# ImageProc.net
KiCad netlist of a schematic drawn in EAGLE
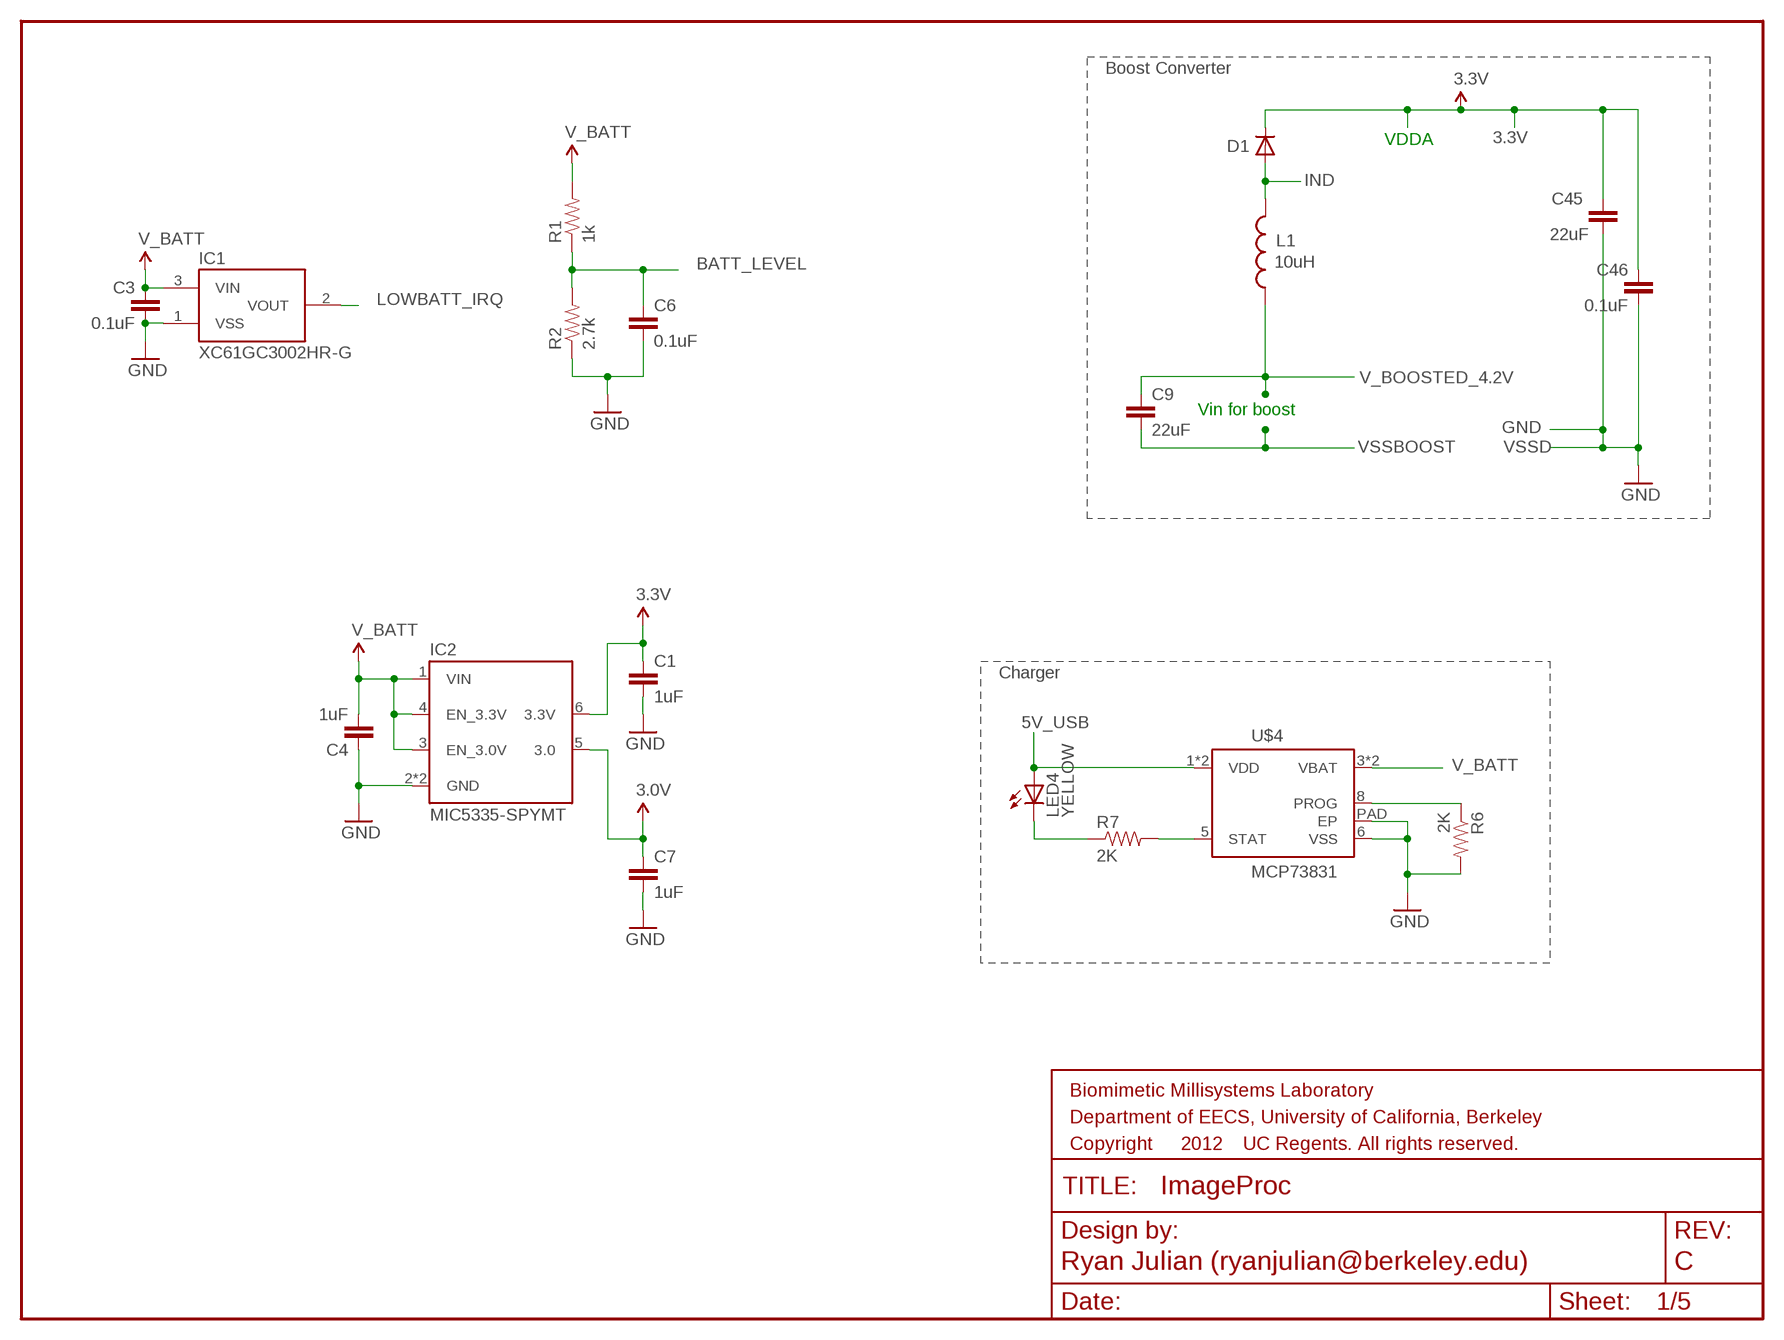
[diagram p0: schematic, sheet 1]
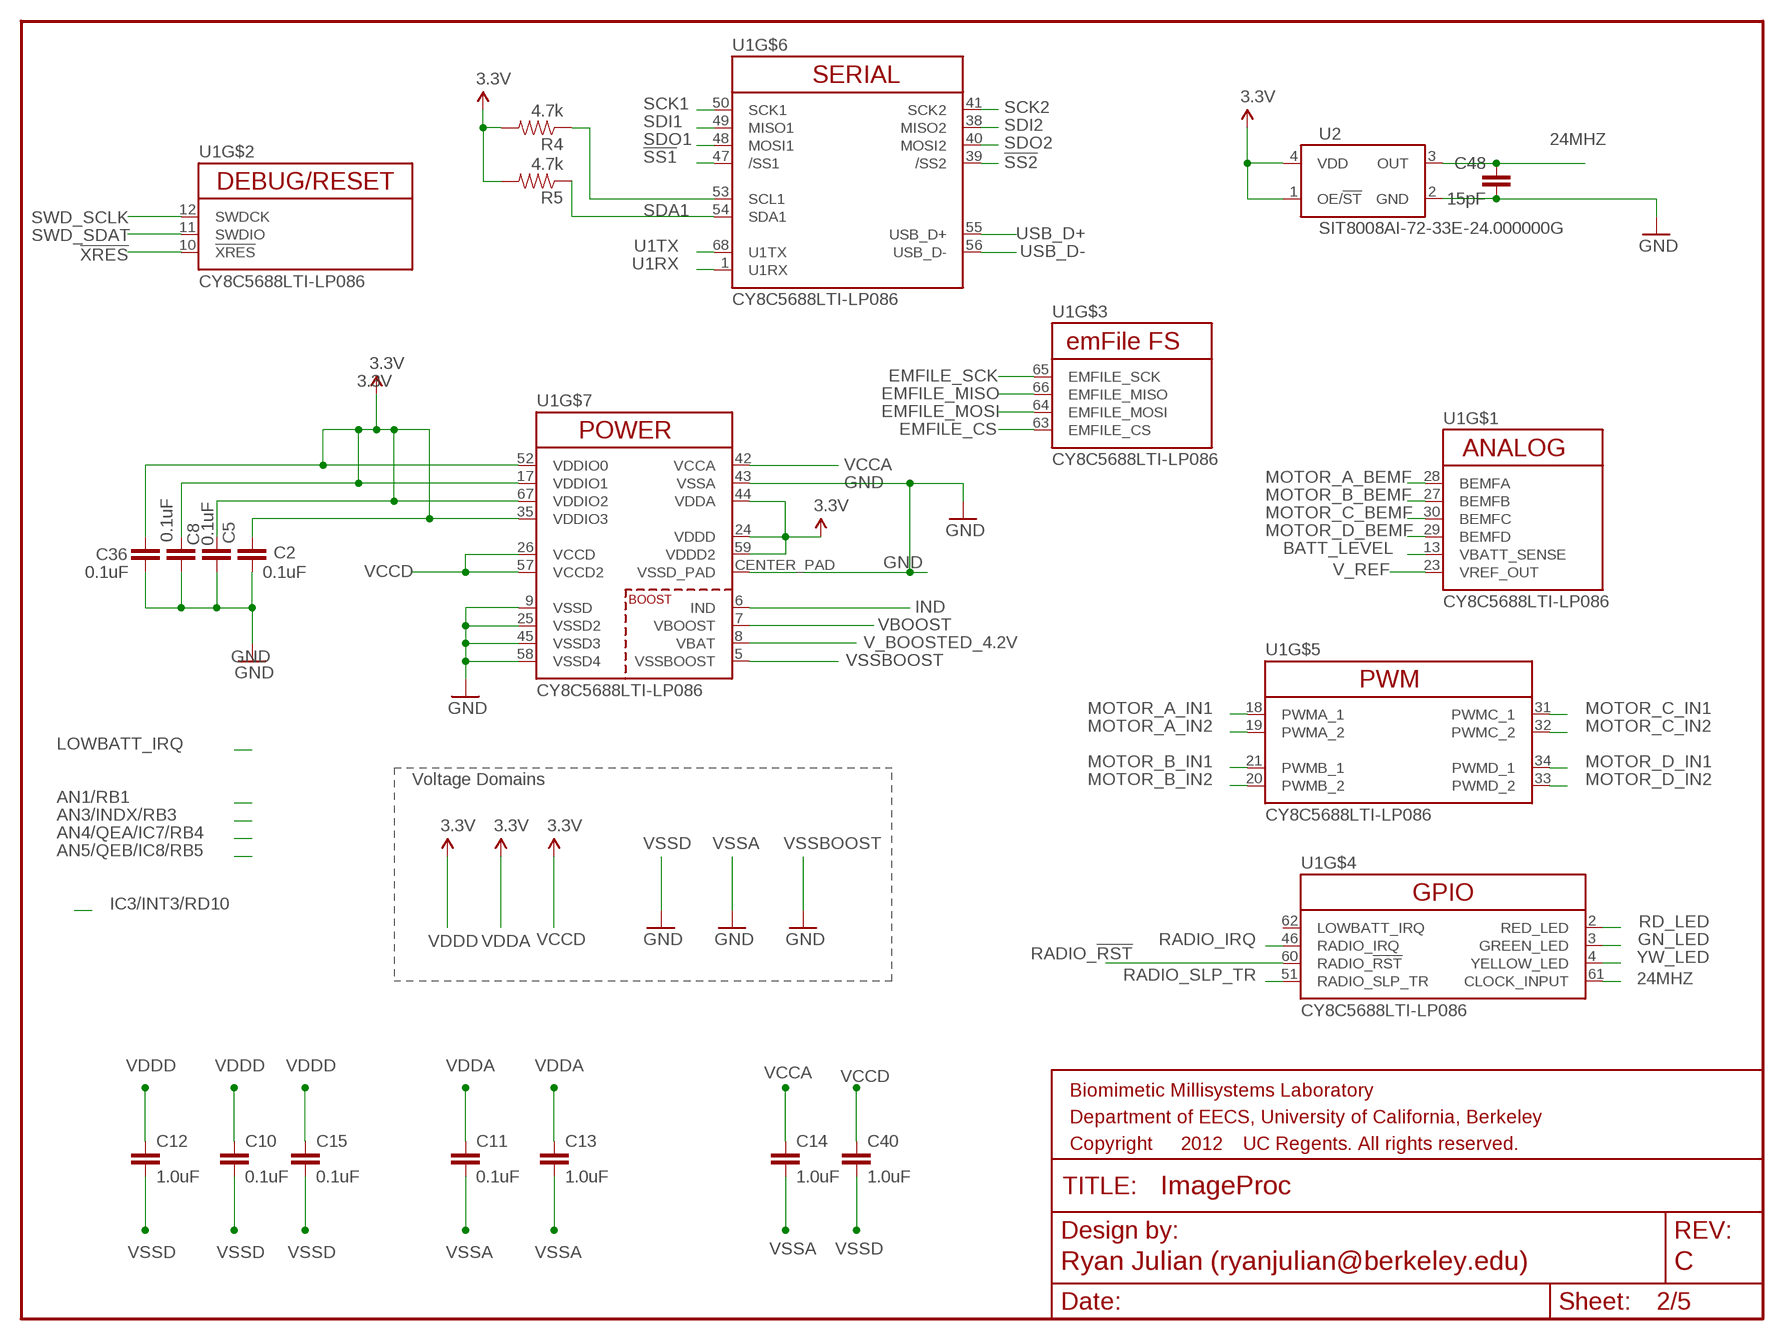
[diagram p1: schematic, sheet 2]
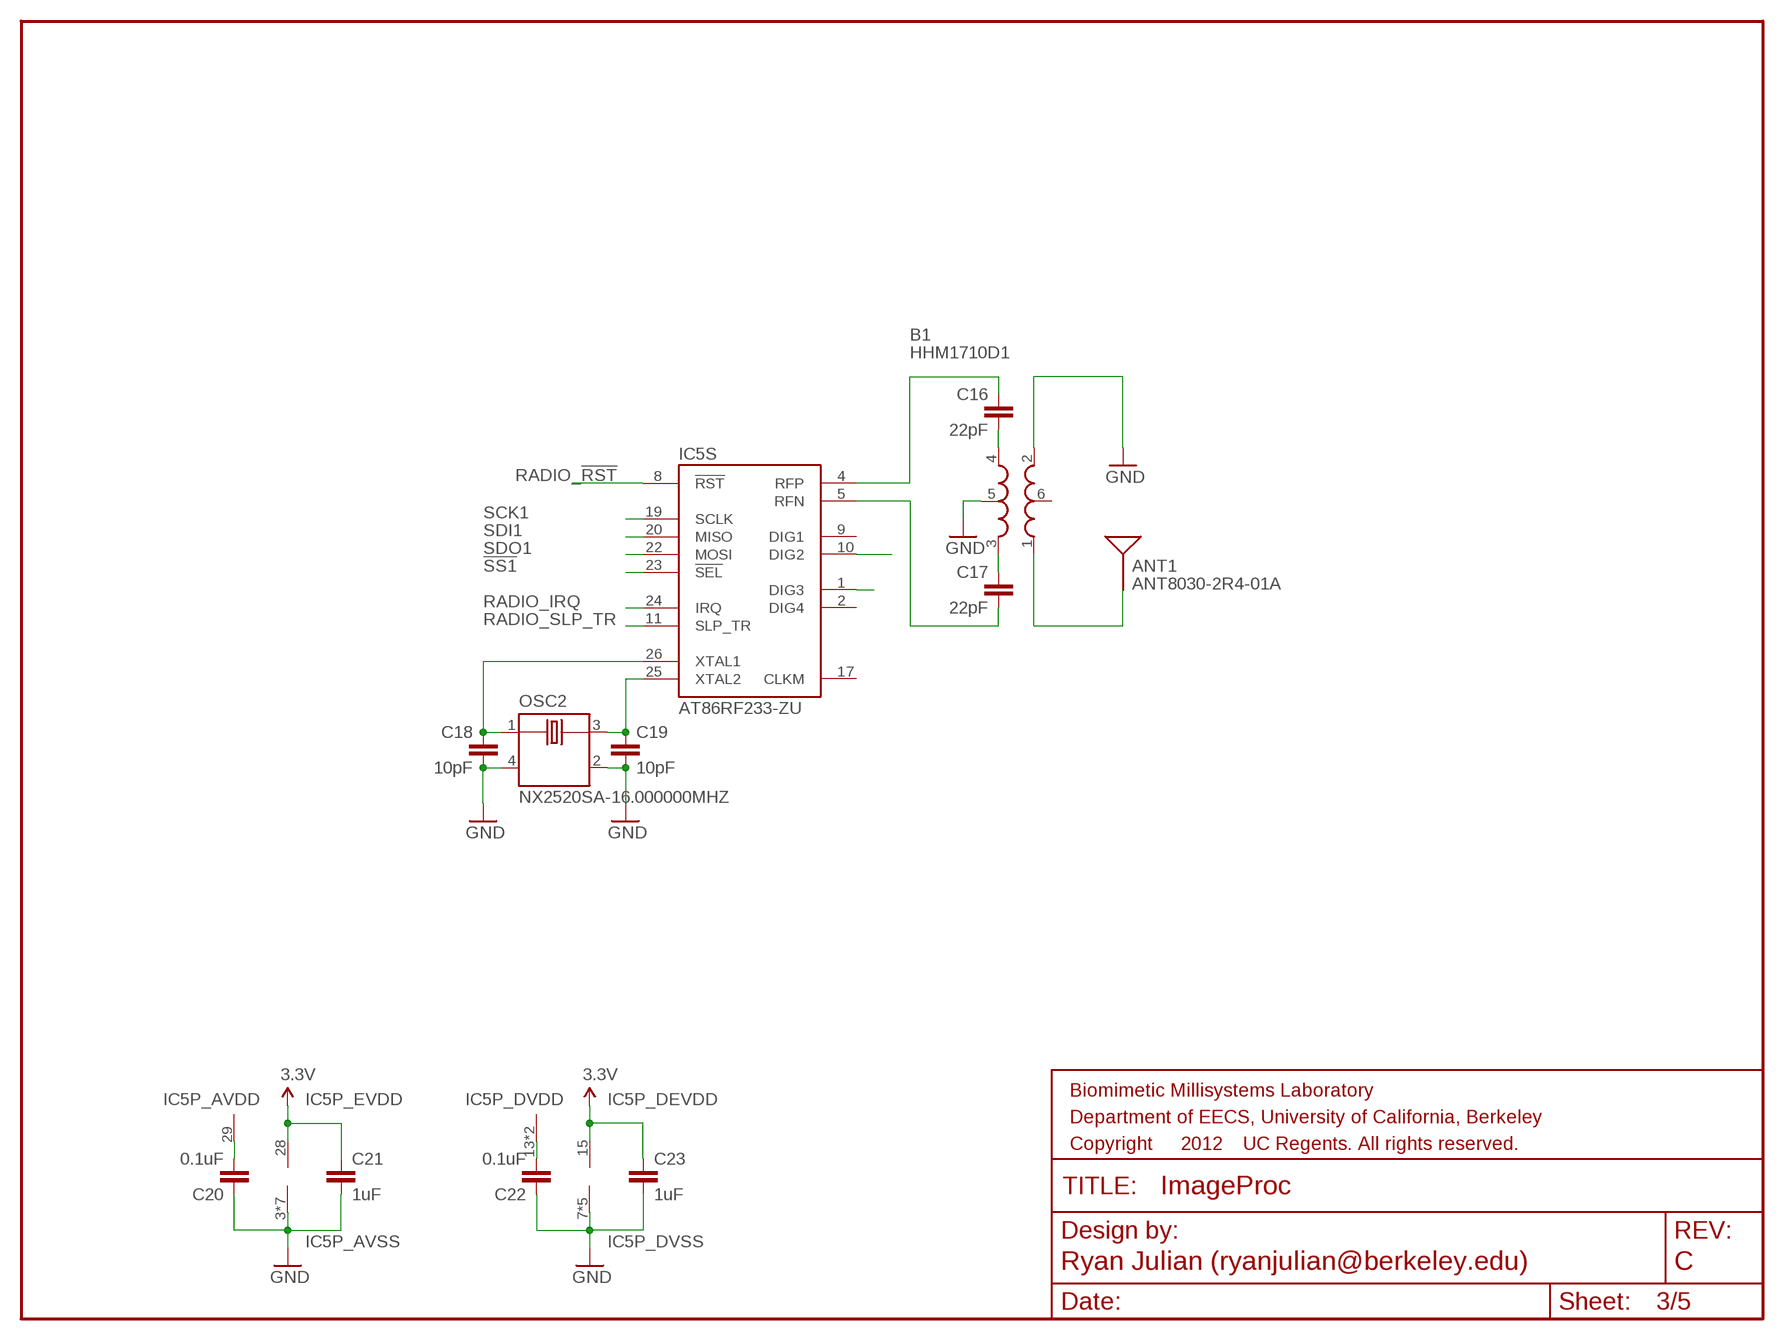
[diagram p2: schematic, sheet 3]
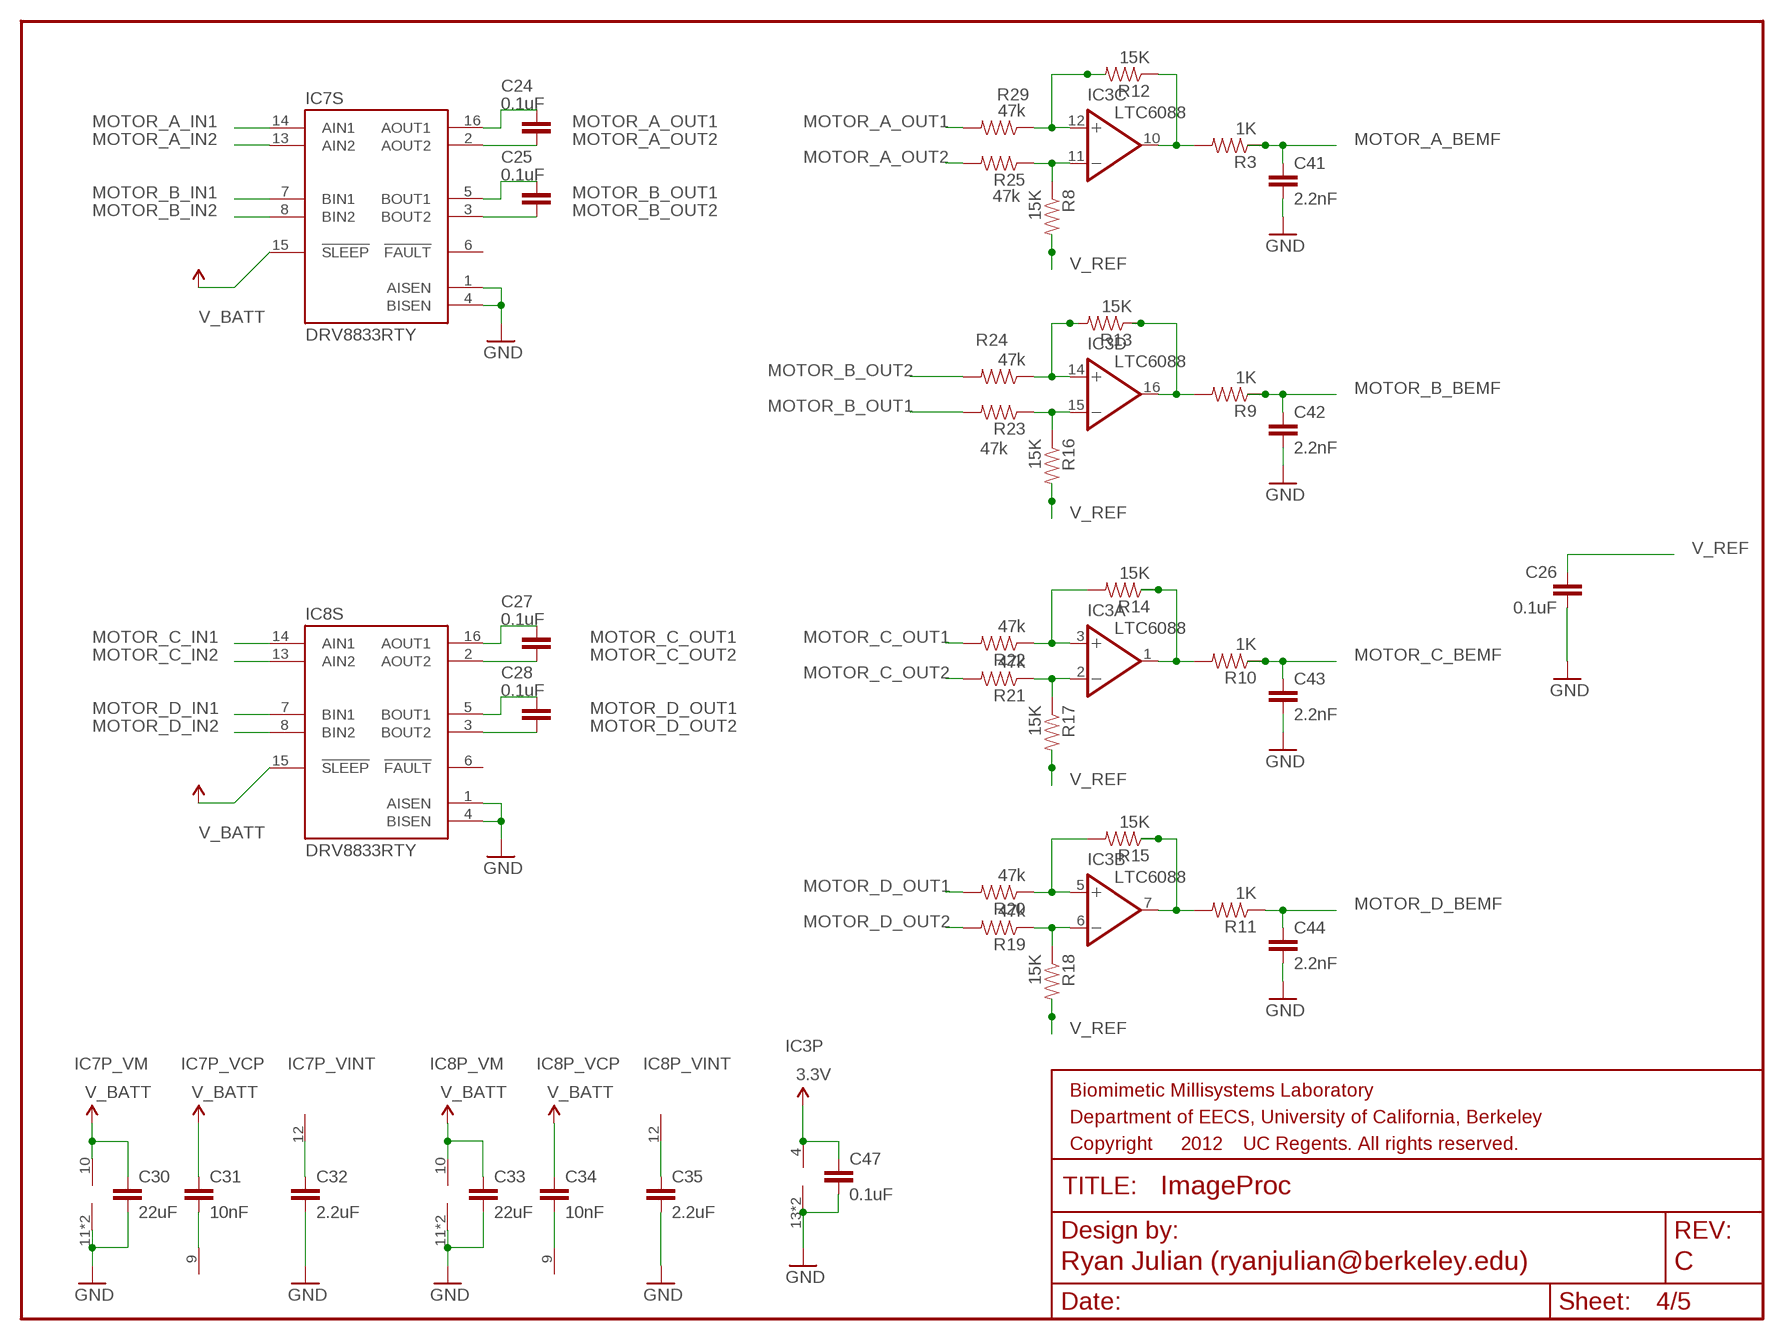
[diagram p3: schematic, sheet 4]
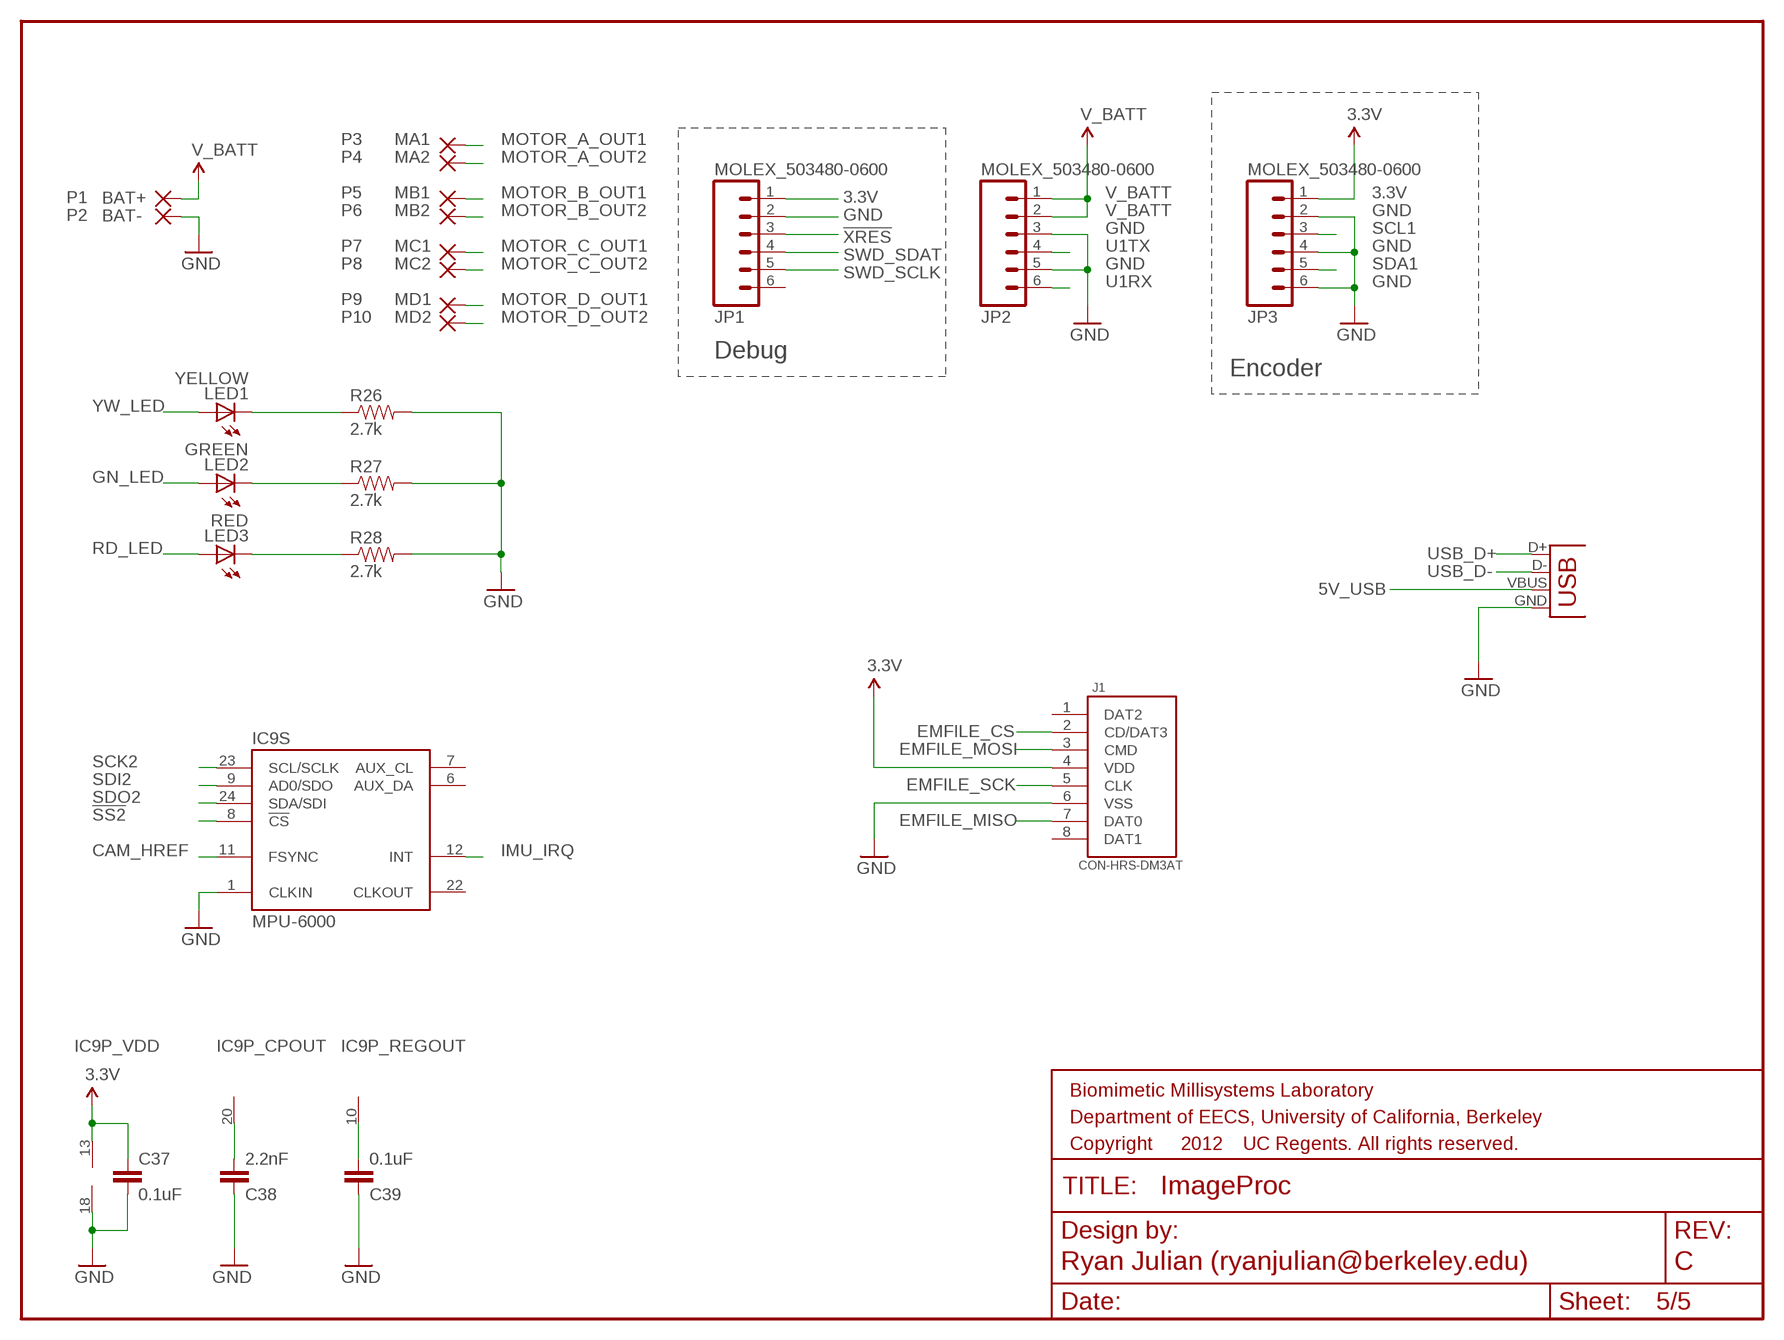
[diagram p4: schematic, sheet 5]

(export (version "E")
  (design (tool "Eeschema 10.0.6"))
  (components
    (comp (ref "C24")
      (value "0.1uF")
      (footprint "eagle-import:0402-CAP")
      (fields (field (name "VOLTAGE") "10V"))
      (libsource (lib "eagle-import") (part "CAP0402-CAP"))
    )
    (comp (ref "C25")
      (value "0.1uF")
      (footprint "eagle-import:0402-CAP")
      (fields (field (name "VOLTAGE") "10V"))
      (libsource (lib "eagle-import") (part "CAP0402-CAP"))
    )
    (comp (ref "C26")
      (value "0.1uF")
      (footprint "eagle-import:0402-CAP")
      (libsource (lib "eagle-import") (part "CAP0402-CAP"))
    )
    (comp (ref "C27")
      (value "0.1uF")
      (footprint "eagle-import:0402-CAP")
      (fields (field (name "VOLTAGE") "10V"))
      (libsource (lib "eagle-import") (part "CAP0402-CAP"))
    )
    (comp (ref "C28")
      (value "0.1uF")
      (footprint "eagle-import:0402-CAP")
      (fields (field (name "VOLTAGE") "10V"))
      (libsource (lib "eagle-import") (part "CAP0402-CAP"))
    )
    (comp (ref "C30")
      (value "22uF")
      (footprint "eagle-import:0603-CAP")
      (libsource (lib "eagle-import") (part "CAP0603-CAP"))
    )
    (comp (ref "C31")
      (value "10nF")
      (footprint "eagle-import:0402-CAP")
      (fields (field (name "VOLTAGE") "16V"))
      (libsource (lib "eagle-import") (part "CAP0402-CAP"))
    )
    (comp (ref "C32")
      (value "2.2uF")
      (footprint "eagle-import:0402-CAP")
      (fields (field (name "VOLTAGE") "6.3V"))
      (libsource (lib "eagle-import") (part "CAP0402-CAP"))
    )
    (comp (ref "C33")
      (value "22uF")
      (footprint "eagle-import:0603-CAP")
      (libsource (lib "eagle-import") (part "CAP0603-CAP"))
    )
    (comp (ref "C34")
      (value "10nF")
      (footprint "eagle-import:0402-CAP")
      (fields (field (name "VOLTAGE") "16V"))
      (libsource (lib "eagle-import") (part "CAP0402-CAP"))
    )
    (comp (ref "C35")
      (value "2.2uF")
      (footprint "eagle-import:0402-CAP")
      (fields (field (name "VOLTAGE") "6.3V"))
      (libsource (lib "eagle-import") (part "CAP0402-CAP"))
    )
    (comp (ref "C41")
      (value "2.2nF")
      (footprint "eagle-import:0402-CAP")
      (libsource (lib "eagle-import") (part "CAP0402-CAP"))
    )
    (comp (ref "C42")
      (value "2.2nF")
      (footprint "eagle-import:0402-CAP")
      (libsource (lib "eagle-import") (part "CAP0402-CAP"))
    )
    (comp (ref "C43")
      (value "2.2nF")
      (footprint "eagle-import:0402-CAP")
      (libsource (lib "eagle-import") (part "CAP0402-CAP"))
    )
    (comp (ref "C44")
      (value "2.2nF")
      (footprint "eagle-import:0402-CAP")
      (libsource (lib "eagle-import") (part "CAP0402-CAP"))
    )
    (comp (ref "C47")
      (value "0.1uF")
      (footprint "eagle-import:0402-CAP")
      (libsource (lib "eagle-import") (part "CAP0402-CAP"))
    )
    (comp (ref "IC3")
      (value "LTC6088")
      (footprint "eagle-import:DFN-16")
      (libsource (lib "eagle-import") (part "LTC6088"))
    )
    (comp (ref "IC7")
      (value "DRV8833RTY")
      (footprint "eagle-import:S-PWQFN-N16")
      (libsource (lib "eagle-import") (part "DRV8833RTY"))
    )
    (comp (ref "IC8")
      (value "DRV8833RTY")
      (footprint "eagle-import:S-PWQFN-N16")
      (libsource (lib "eagle-import") (part "DRV8833RTY"))
    )
    (comp (ref "R3")
      (value "1K")
      (footprint "eagle-import:0402-RES")
      (libsource (lib "eagle-import") (part "RESISTOR0402-RES"))
    )
    (comp (ref "R8")
      (value "15K")
      (footprint "eagle-import:0402-RES")
      (libsource (lib "eagle-import") (part "RESISTOR0402-RES"))
    )
    (comp (ref "R9")
      (value "1K")
      (footprint "eagle-import:0402-RES")
      (libsource (lib "eagle-import") (part "RESISTOR0402-RES"))
    )
    (comp (ref "R10")
      (value "1K")
      (footprint "eagle-import:0402-RES")
      (libsource (lib "eagle-import") (part "RESISTOR0402-RES"))
    )
    (comp (ref "R11")
      (value "1K")
      (footprint "eagle-import:0402-RES")
      (libsource (lib "eagle-import") (part "RESISTOR0402-RES"))
    )
    (comp (ref "R12")
      (value "15K")
      (footprint "eagle-import:0402-RES")
      (libsource (lib "eagle-import") (part "RESISTOR0402-RES"))
    )
    (comp (ref "R13")
      (value "15K")
      (footprint "eagle-import:0402-RES")
      (libsource (lib "eagle-import") (part "RESISTOR0402-RES"))
    )
    (comp (ref "R14")
      (value "15K")
      (footprint "eagle-import:0402-RES")
      (libsource (lib "eagle-import") (part "RESISTOR0402-RES"))
    )
    (comp (ref "R15")
      (value "15K")
      (footprint "eagle-import:0402-RES")
      (libsource (lib "eagle-import") (part "RESISTOR0402-RES"))
    )
    (comp (ref "R16")
      (value "15K")
      (footprint "eagle-import:0402-RES")
      (libsource (lib "eagle-import") (part "RESISTOR0402-RES"))
    )
    (comp (ref "R17")
      (value "15K")
      (footprint "eagle-import:0402-RES")
      (libsource (lib "eagle-import") (part "RESISTOR0402-RES"))
    )
    (comp (ref "R18")
      (value "15K")
      (footprint "eagle-import:0402-RES")
      (libsource (lib "eagle-import") (part "RESISTOR0402-RES"))
    )
    (comp (ref "R19")
      (value "47k")
      (footprint "eagle-import:0402-RES")
      (libsource (lib "eagle-import") (part "RESISTOR0402-RES"))
    )
    (comp (ref "R20")
      (value "47k")
      (footprint "eagle-import:0402-RES")
      (libsource (lib "eagle-import") (part "RESISTOR0402-RES"))
    )
    (comp (ref "R21")
      (value "47k")
      (footprint "eagle-import:0402-RES")
      (libsource (lib "eagle-import") (part "RESISTOR0402-RES"))
    )
    (comp (ref "R22")
      (value "47k")
      (footprint "eagle-import:0402-RES")
      (libsource (lib "eagle-import") (part "RESISTOR0402-RES"))
    )
    (comp (ref "R23")
      (value "47k")
      (footprint "eagle-import:0402-RES")
      (libsource (lib "eagle-import") (part "RESISTOR0402-RES"))
    )
    (comp (ref "R24")
      (value "47k")
      (footprint "eagle-import:0402-RES")
      (libsource (lib "eagle-import") (part "RESISTOR0402-RES"))
    )
    (comp (ref "R25")
      (value "47k")
      (footprint "eagle-import:0402-RES")
      (libsource (lib "eagle-import") (part "RESISTOR0402-RES"))
    )
    (comp (ref "R29")
      (value "47k")
      (footprint "eagle-import:0402-RES")
      (libsource (lib "eagle-import") (part "RESISTOR0402-RES"))
    )
    (comp (ref "ANT1")
      (value "ANT8030-2R4-01A")
      (footprint "eagle-import:ANT8030-2R4-01A")
      (libsource (lib "eagle-import") (part "ANT8030-2R4-01A"))
    )
    (comp (ref "B1")
      (value "HHM1710D1")
      (footprint "eagle-import:0603-BALUN")
      (libsource (lib "eagle-import") (part "HHM1710D1"))
    )
    (comp (ref "C16")
      (value "22pF")
      (footprint "eagle-import:0402-CAP")
      (fields (field (name "TOLERANCE") "5%") (field (name "VOLTAGE") "50V"))
      (libsource (lib "eagle-import") (part "CAP0402-CAP"))
    )
    (comp (ref "C17")
      (value "22pF")
      (footprint "eagle-import:0402-CAP")
      (fields (field (name "TOLERANCE") "5%") (field (name "VOLTAGE") "50V"))
      (libsource (lib "eagle-import") (part "CAP0402-CAP"))
    )
    (comp (ref "C18")
      (value "10pF")
      (footprint "eagle-import:0402-CAP")
      (fields (field (name "TOLERANCE") "10%") (field (name "VOLTAGE") "50V"))
      (libsource (lib "eagle-import") (part "CAP0402-CAP"))
    )
    (comp (ref "C19")
      (value "10pF")
      (footprint "eagle-import:0402-CAP")
      (fields (field (name "TOLERANCE") "10%") (field (name "VOLTAGE") "50V"))
      (libsource (lib "eagle-import") (part "CAP0402-CAP"))
    )
    (comp (ref "C20")
      (value "0.1uF")
      (footprint "eagle-import:0402-CAP")
      (fields (field (name "TOLERANCE") "10%") (field (name "VOLTAGE") "16V"))
      (libsource (lib "eagle-import") (part "CAP0402-CAP"))
    )
    (comp (ref "C21")
      (value "1uF")
      (footprint "eagle-import:0402-CAP")
      (fields (field (name "TOLERANCE") "10%") (field (name "VOLTAGE") "16V"))
      (libsource (lib "eagle-import") (part "CAP0402-CAP"))
    )
    (comp (ref "C22")
      (value "0.1uF")
      (footprint "eagle-import:0402-CAP")
      (fields (field (name "TOLERANCE") "10%") (field (name "VOLTAGE") "16V"))
      (libsource (lib "eagle-import") (part "CAP0402-CAP"))
    )
    (comp (ref "C23")
      (value "1uF")
      (footprint "eagle-import:0402-CAP")
      (fields (field (name "TOLERANCE") "10%") (field (name "VOLTAGE") "16V"))
      (libsource (lib "eagle-import") (part "CAP0402-CAP"))
    )
    (comp (ref "IC5")
      (value "AT86RF233-ZU")
      (footprint "eagle-import:VQFN-32QN2")
      (libsource (lib "eagle-import") (part "AT86RF233-ZU"))
    )
    (comp (ref "OSC2")
      (value "NX2520SA-16.000000MHZ")
      (footprint "eagle-import:CRYSTAL-SMD")
      (libsource (lib "eagle-import") (part "NX2520SA-16.000000MHZ"))
    )
    (comp (ref "C1")
      (value "1uF")
      (footprint "eagle-import:0402-CAP")
      (libsource (lib "eagle-import") (part "CAP0402-CAP"))
    )
    (comp (ref "C3")
      (value "0.1uF")
      (footprint "eagle-import:0402-CAP")
      (libsource (lib "eagle-import") (part "CAP0402-CAP"))
    )
    (comp (ref "C4")
      (value "1uF")
      (footprint "eagle-import:0402-CAP")
      (libsource (lib "eagle-import") (part "CAP0402-CAP"))
    )
    (comp (ref "C6")
      (value "0.1uF")
      (footprint "eagle-import:0402-CAP")
      (libsource (lib "eagle-import") (part "CAP0402-CAP"))
    )
    (comp (ref "C7")
      (value "1uF")
      (footprint "eagle-import:0402-CAP")
      (libsource (lib "eagle-import") (part "CAP0402-CAP"))
    )
    (comp (ref "C9")
      (value "22uF")
      (footprint "eagle-import:0805")
      (libsource (lib "eagle-import") (part "CAP0805"))
    )
    (comp (ref "C45")
      (value "22uF")
      (footprint "eagle-import:0805")
      (libsource (lib "eagle-import") (part "CAP0805"))
    )
    (comp (ref "C46")
      (value "0.1uF")
      (footprint "eagle-import:0402-CAP")
      (libsource (lib "eagle-import") (part "CAP0402-CAP"))
    )
    (comp (ref "D1")
      (value "DIODE-SOD123")
      (footprint "eagle-import:SOD123")
      (libsource (lib "eagle-import") (part "DIODE-SOD123"))
    )
    (comp (ref "IC1")
      (value "XC61GC3002HR-G")
      (footprint "eagle-import:USP-3")
      (libsource (lib "eagle-import") (part "XC61GC3002HR-G"))
    )
    (comp (ref "IC2")
      (value "MIC5335-SPYMT")
      (footprint "eagle-import:MLF-6")
      (libsource (lib "eagle-import") (part "MIC5335-SPYMT"))
    )
    (comp (ref "L1")
      (value "10uH")
      (footprint "eagle-import:INDUCTOR_SMD_3X3")
      (libsource (lib "eagle-import") (part "SRN3015-100M"))
    )
    (comp (ref "LED4")
      (value "YELLOW")
      (footprint "eagle-import:LED-0603")
      (libsource (lib "eagle-import") (part "LED0603"))
    )
    (comp (ref "R1")
      (value "1k")
      (footprint "eagle-import:0402-RES")
      (libsource (lib "eagle-import") (part "RESISTOR0402-RES"))
    )
    (comp (ref "R2")
      (value "2.7k")
      (footprint "eagle-import:0402-RES")
      (libsource (lib "eagle-import") (part "RESISTOR0402-RES"))
    )
    (comp (ref "R6")
      (value "2K")
      (footprint "eagle-import:0402-RES")
      (libsource (lib "eagle-import") (part "RESISTOR0402-RES"))
    )
    (comp (ref "R7")
      (value "2K")
      (footprint "eagle-import:0402-RES")
      (libsource (lib "eagle-import") (part "RESISTOR0402-RES"))
    )
    (comp (ref "U$4")
      (value "MCP73831")
      (footprint "eagle-import:DFN-8")
      (libsource (lib "eagle-import") (part "MCP73831"))
    )
    (comp (ref "C37")
      (value "0.1uF")
      (footprint "eagle-import:0402-CAP")
      (fields (field (name "TOLERANCE") "10%") (field (name "VOLTAGE") "4V"))
      (libsource (lib "eagle-import") (part "CAP0402-CAP"))
    )
    (comp (ref "C38")
      (value "2.2nF")
      (footprint "eagle-import:0402-CAP")
      (fields (field (name "TOLERANCE") "10%") (field (name "VOLTAGE") "50V"))
      (libsource (lib "eagle-import") (part "CAP0402-CAP"))
    )
    (comp (ref "C39")
      (value "0.1uF")
      (footprint "eagle-import:0402-CAP")
      (fields (field (name "TOLERANCE") "10%") (field (name "VOLTAGE") "2V"))
      (libsource (lib "eagle-import") (part "CAP0402-CAP"))
    )
    (comp (ref "IC9")
      (value "MPU-6000")
      (footprint "eagle-import:QFN-24")
      (libsource (lib "eagle-import") (part "MPU-6000"))
    )
    (comp (ref "J1")
      (value "CON-HRS-DM3AT")
      (footprint "eagle-import:HRS-DM3AT")
      (fields (field (name "MF") "Hirose") (field (name "MPN") "DM3AT-SF-PEJM5"))
      (libsource (lib "eagle-import") (part "CON-HRS-DM3AT"))
    )
    (comp (ref "JP1")
      (value "MOLEX_503480-0600")
      (footprint "eagle-import:MOLEX_503480-0600")
      (libsource (lib "eagle-import") (part "MOLEX_503480-0600"))
    )
    (comp (ref "JP2")
      (value "MOLEX_503480-0600")
      (footprint "eagle-import:MOLEX_503480-0600")
      (libsource (lib "eagle-import") (part "MOLEX_503480-0600"))
    )
    (comp (ref "JP3")
      (value "MOLEX_503480-0600")
      (footprint "eagle-import:MOLEX_503480-0600")
      (libsource (lib "eagle-import") (part "MOLEX_503480-0600"))
    )
    (comp (ref "JP6")
      (value "USBSMD")
      (footprint "eagle-import:USB-MINIB")
      (libsource (lib "eagle-import") (part "USBSMD"))
    )
    (comp (ref "LED1")
      (value "YELLOW")
      (footprint "eagle-import:LED-0603")
      (libsource (lib "eagle-import") (part "LED0603"))
    )
    (comp (ref "LED2")
      (value "GREEN")
      (footprint "eagle-import:LED-0603")
      (libsource (lib "eagle-import") (part "LED0603"))
    )
    (comp (ref "LED3")
      (value "RED")
      (footprint "eagle-import:LED-0603")
      (libsource (lib "eagle-import") (part "LED0603"))
    )
    (comp (ref "P1")
      (value "BAT+")
      (footprint "eagle-import:SMD1,27-2,54")
      (libsource (lib "eagle-import") (part "SMD2"))
    )
    (comp (ref "P2")
      (value "BAT-")
      (footprint "eagle-import:SMD1,27-2,54")
      (libsource (lib "eagle-import") (part "SMD2"))
    )
    (comp (ref "P3")
      (value "MA1")
      (footprint "eagle-import:SMD1,27-2,54")
      (libsource (lib "eagle-import") (part "SMD2"))
    )
    (comp (ref "P4")
      (value "MA2")
      (footprint "eagle-import:SMD1,27-2,54")
      (libsource (lib "eagle-import") (part "SMD2"))
    )
    (comp (ref "P5")
      (value "MB1")
      (footprint "eagle-import:SMD1,27-2,54")
      (libsource (lib "eagle-import") (part "SMD2"))
    )
    (comp (ref "P6")
      (value "MB2")
      (footprint "eagle-import:SMD1,27-2,54")
      (libsource (lib "eagle-import") (part "SMD2"))
    )
    (comp (ref "P7")
      (value "MC1")
      (footprint "eagle-import:SMD1,27-2,54")
      (libsource (lib "eagle-import") (part "SMD2"))
    )
    (comp (ref "P8")
      (value "MC2")
      (footprint "eagle-import:SMD1,27-2,54")
      (libsource (lib "eagle-import") (part "SMD2"))
    )
    (comp (ref "P9")
      (value "MD1")
      (footprint "eagle-import:SMD1,27-2,54")
      (libsource (lib "eagle-import") (part "SMD2"))
    )
    (comp (ref "P10")
      (value "MD2")
      (footprint "eagle-import:SMD1,27-2,54")
      (libsource (lib "eagle-import") (part "SMD2"))
    )
    (comp (ref "R26")
      (value "2.7k")
      (footprint "eagle-import:0402-RES")
      (libsource (lib "eagle-import") (part "RESISTOR0402-RES"))
    )
    (comp (ref "R27")
      (value "2.7k")
      (footprint "eagle-import:0402-RES")
      (libsource (lib "eagle-import") (part "RESISTOR0402-RES"))
    )
    (comp (ref "R28")
      (value "2.7k")
      (footprint "eagle-import:0402-RES")
      (libsource (lib "eagle-import") (part "RESISTOR0402-RES"))
    )
    (comp (ref "C2")
      (value "0.1uF")
      (footprint "eagle-import:0402-CAP")
      (libsource (lib "eagle-import") (part "CAP0402-CAP"))
    )
    (comp (ref "C5")
      (value "0.1uF")
      (footprint "eagle-import:0402-CAP")
      (libsource (lib "eagle-import") (part "CAP0402-CAP"))
    )
    (comp (ref "C8")
      (value "0.1uF")
      (footprint "eagle-import:0402-CAP")
      (libsource (lib "eagle-import") (part "CAP0402-CAP"))
    )
    (comp (ref "C10")
      (value "0.1uF")
      (footprint "eagle-import:0402-CAP")
      (libsource (lib "eagle-import") (part "CAP0402-CAP"))
    )
    (comp (ref "C11")
      (value "0.1uF")
      (footprint "eagle-import:0402-CAP")
      (libsource (lib "eagle-import") (part "CAP0402-CAP"))
    )
    (comp (ref "C12")
      (value "1.0uF")
      (footprint "eagle-import:0402-CAP")
      (libsource (lib "eagle-import") (part "CAP0402-CAP"))
    )
    (comp (ref "C13")
      (value "1.0uF")
      (footprint "eagle-import:0402-CAP")
      (libsource (lib "eagle-import") (part "CAP0402-CAP"))
    )
    (comp (ref "C14")
      (value "1.0uF")
      (footprint "eagle-import:0402-CAP")
      (libsource (lib "eagle-import") (part "CAP0402-CAP"))
    )
    (comp (ref "C15")
      (value "0.1uF")
      (footprint "eagle-import:0402-CAP")
      (libsource (lib "eagle-import") (part "CAP0402-CAP"))
    )
    (comp (ref "C36")
      (value "0.1uF")
      (footprint "eagle-import:0402-CAP")
      (libsource (lib "eagle-import") (part "CAP0402-CAP"))
    )
    (comp (ref "C40")
      (value "1.0uF")
      (footprint "eagle-import:0402-CAP")
      (libsource (lib "eagle-import") (part "CAP0402-CAP"))
    )
    (comp (ref "C48")
      (value "15pF")
      (footprint "eagle-import:0402-CAP")
      (fields (field (name "TOLERANCE") "5%") (field (name "VOLTAGE") "50V"))
      (libsource (lib "eagle-import") (part "CAP0402-CAP"))
    )
    (comp (ref "R4")
      (value "4.7k")
      (footprint "eagle-import:0402-RES")
      (libsource (lib "eagle-import") (part "RESISTOR0402-RES"))
    )
    (comp (ref "R5")
      (value "4.7k")
      (footprint "eagle-import:0402-RES")
      (libsource (lib "eagle-import") (part "RESISTOR0402-RES"))
    )
    (comp (ref "U1")
      (value "CY8C5688LTI-LP086")
      (footprint "eagle-import:68QFN")
      (libsource (lib "eagle-import") (part "CY8C5688LTI-LP086"))
    )
    (comp (ref "U2")
      (value "SIT8008AI-72-33E-24.000000G")
      (footprint "eagle-import:4-SMD")
      (libsource (lib "eagle-import") (part "SIT8008AI-72-33E-24.000000G"))
    )
  )
  (nets
    (net (code "1") (name "3.0V") (class "Default")
      (node (ref "C7") (pin "1") (pinfunction "1_1") (pintype "passive"))
      (node (ref "IC2") (pin "5") (pinfunction "3.0_5") (pintype "bidirectional"))
    )
    (net (code "2") (name "3.3V") (class "Default")
      (node (ref "C1") (pin "1") (pinfunction "1_1") (pintype "passive"))
      (node (ref "C10") (pin "1") (pinfunction "1_1") (pintype "passive"))
      (node (ref "C11") (pin "1") (pinfunction "1_1") (pintype "passive"))
      (node (ref "C12") (pin "1") (pinfunction "1_1") (pintype "passive"))
      (node (ref "C13") (pin "1") (pinfunction "1_1") (pintype "passive"))
      (node (ref "C15") (pin "1") (pinfunction "1_1") (pintype "passive"))
      (node (ref "C2") (pin "1") (pinfunction "1_1") (pintype "passive"))
      (node (ref "C21") (pin "1") (pinfunction "1_1") (pintype "passive"))
      (node (ref "C23") (pin "1") (pinfunction "1_1") (pintype "passive"))
      (node (ref "C36") (pin "1") (pinfunction "1_1") (pintype "passive"))
      (node (ref "C37") (pin "1") (pinfunction "1_1") (pintype "passive"))
      (node (ref "C45") (pin "1") (pinfunction "1_1") (pintype "passive"))
      (node (ref "C46") (pin "1") (pinfunction "1_1") (pintype "passive"))
      (node (ref "C47") (pin "1") (pinfunction "1_1") (pintype "passive"))
      (node (ref "C5") (pin "1") (pinfunction "1_1") (pintype "passive"))
      (node (ref "C8") (pin "1") (pinfunction "1_1") (pintype "passive"))
      (node (ref "D1") (pin "C") (pinfunction "C_C") (pintype "passive"))
      (node (ref "IC2") (pin "6") (pinfunction "3.3V_6") (pintype "bidirectional"))
      (node (ref "IC3") (pin "4") (pinfunction "V+_4") (pintype "power_in"))
      (node (ref "IC5") (pin "15") (pinfunction "V+_15") (pintype "power_in"))
      (node (ref "IC5") (pin "28") (pinfunction "V+_28") (pintype "power_in"))
      (node (ref "IC9") (pin "13") (pinfunction "V+_13") (pintype "power_in"))
      (node (ref "J1") (pin "4") (pinfunction "VDD_4") (pintype "power_in"))
      (node (ref "JP1") (pin "1") (pinfunction "1_1") (pintype "passive"))
      (node (ref "JP3") (pin "1") (pinfunction "1_1") (pintype "passive"))
      (node (ref "R4") (pin "2") (pinfunction "2_2") (pintype "passive"))
      (node (ref "R5") (pin "2") (pinfunction "2_2") (pintype "passive"))
      (node (ref "U1") (pin "17") (pinfunction "VDDIO1_17") (pintype "bidirectional"))
      (node (ref "U1") (pin "24") (pinfunction "VDDD_24") (pintype "bidirectional"))
      (node (ref "U1") (pin "35") (pinfunction "VDDIO3_35") (pintype "bidirectional"))
      (node (ref "U1") (pin "44") (pinfunction "VDDA_44") (pintype "bidirectional"))
      (node (ref "U1") (pin "52") (pinfunction "VDDIO0_52") (pintype "bidirectional"))
      (node (ref "U1") (pin "59") (pinfunction "VDDD2_59") (pintype "bidirectional"))
      (node (ref "U1") (pin "67") (pinfunction "VDDIO2_67") (pintype "bidirectional"))
      (node (ref "U2") (pin "1") (pinfunction "OE/~{ST}_1") (pintype "bidirectional"))
      (node (ref "U2") (pin "4") (pinfunction "VDD_4") (pintype "bidirectional"))
    )
    (net (code "3") (name "5V_USB") (class "Default")
      (node (ref "JP6") (pin "VBUS") (pinfunction "VBUS_VBUS") (pintype "bidirectional"))
      (node (ref "LED4") (pin "A") (pinfunction "A_A") (pintype "passive"))
      (node (ref "U$4") (pin "1") (pinfunction "VDD_1") (pintype "bidirectional"))
      (node (ref "U$4") (pin "2") (pinfunction "VDD_2") (pintype "bidirectional"))
    )
    (net (code "4") (name "24MHZ") (class "Default")
      (node (ref "C48") (pin "1") (pinfunction "1_1") (pintype "passive"))
      (node (ref "U1") (pin "61") (pinfunction "CLOCK_INPUT_61") (pintype "bidirectional"))
      (node (ref "U2") (pin "3") (pinfunction "OUT_3") (pintype "bidirectional"))
    )
    (net (code "9") (name "BATT_LEVEL") (class "Default")
      (node (ref "C6") (pin "1") (pinfunction "1_1") (pintype "passive"))
      (node (ref "R1") (pin "1") (pinfunction "1_1") (pintype "passive"))
      (node (ref "R2") (pin "2") (pinfunction "2_2") (pintype "passive"))
      (node (ref "U1") (pin "13") (pinfunction "VBATT_SENSE_13") (pintype "bidirectional"))
    )
    (net (code "10") (name "CAM_HREF") (class "Default")
      (node (ref "IC9") (pin "11") (pinfunction "FSYNC_11") (pintype "bidirectional"))
    )
    (net (code "11") (name "EMFILE_CS") (class "Default")
      (node (ref "J1") (pin "2") (pinfunction "CD/DAT3_2") (pintype "bidirectional"))
      (node (ref "U1") (pin "63") (pinfunction "EMFILE_CS_63") (pintype "bidirectional"))
    )
    (net (code "12") (name "EMFILE_MISO") (class "Default")
      (node (ref "J1") (pin "7") (pinfunction "DAT0_7") (pintype "bidirectional"))
      (node (ref "U1") (pin "66") (pinfunction "EMFILE_MISO_66") (pintype "bidirectional"))
    )
    (net (code "13") (name "EMFILE_MOSI") (class "Default")
      (node (ref "J1") (pin "3") (pinfunction "CMD_3") (pintype "bidirectional"))
      (node (ref "U1") (pin "64") (pinfunction "EMFILE_MOSI_64") (pintype "bidirectional"))
    )
    (net (code "14") (name "EMFILE_SCK") (class "Default")
      (node (ref "J1") (pin "5") (pinfunction "CLK_5") (pintype "bidirectional"))
      (node (ref "U1") (pin "65") (pinfunction "EMFILE_SCK_65") (pintype "bidirectional"))
    )
    (net (code "15") (name "GND") (class "Default")
      (node (ref "B1") (pin "2") (pinfunction "RFGND_2") (pintype "bidirectional"))
      (node (ref "B1") (pin "5") (pinfunction "GND_5") (pintype "bidirectional"))
      (node (ref "C1") (pin "2") (pinfunction "2_2") (pintype "passive"))
      (node (ref "C10") (pin "2") (pinfunction "2_2") (pintype "passive"))
      (node (ref "C11") (pin "2") (pinfunction "2_2") (pintype "passive"))
      (node (ref "C12") (pin "2") (pinfunction "2_2") (pintype "passive"))
      (node (ref "C14") (pin "2") (pinfunction "2_2") (pintype "passive"))
      (node (ref "C15") (pin "2") (pinfunction "2_2") (pintype "passive"))
      (node (ref "C18") (pin "2") (pinfunction "2_2") (pintype "passive"))
      (node (ref "C19") (pin "2") (pinfunction "2_2") (pintype "passive"))
      (node (ref "C2") (pin "2") (pinfunction "2_2") (pintype "passive"))
      (node (ref "C20") (pin "1") (pinfunction "1_1") (pintype "passive"))
      (node (ref "C21") (pin "2") (pinfunction "2_2") (pintype "passive"))
      (node (ref "C22") (pin "1") (pinfunction "1_1") (pintype "passive"))
      (node (ref "C23") (pin "2") (pinfunction "2_2") (pintype "passive"))
      (node (ref "C26") (pin "2") (pinfunction "2_2") (pintype "passive"))
      (node (ref "C3") (pin "2") (pinfunction "2_2") (pintype "passive"))
      (node (ref "C30") (pin "2") (pinfunction "2_2") (pintype "passive"))
      (node (ref "C32") (pin "2") (pinfunction "2_2") (pintype "passive"))
      (node (ref "C33") (pin "2") (pinfunction "2_2") (pintype "passive"))
      (node (ref "C35") (pin "2") (pinfunction "2_2") (pintype "passive"))
      (node (ref "C36") (pin "2") (pinfunction "2_2") (pintype "passive"))
      (node (ref "C37") (pin "2") (pinfunction "2_2") (pintype "passive"))
      (node (ref "C38") (pin "1") (pinfunction "1_1") (pintype "passive"))
      (node (ref "C39") (pin "1") (pinfunction "1_1") (pintype "passive"))
      (node (ref "C4") (pin "1") (pinfunction "1_1") (pintype "passive"))
      (node (ref "C40") (pin "2") (pinfunction "2_2") (pintype "passive"))
      (node (ref "C41") (pin "2") (pinfunction "2_2") (pintype "passive"))
      (node (ref "C42") (pin "2") (pinfunction "2_2") (pintype "passive"))
      (node (ref "C43") (pin "2") (pinfunction "2_2") (pintype "passive"))
      (node (ref "C44") (pin "2") (pinfunction "2_2") (pintype "passive"))
      (node (ref "C45") (pin "2") (pinfunction "2_2") (pintype "passive"))
      (node (ref "C46") (pin "2") (pinfunction "2_2") (pintype "passive"))
      (node (ref "C47") (pin "2") (pinfunction "2_2") (pintype "passive"))
      (node (ref "C48") (pin "2") (pinfunction "2_2") (pintype "passive"))
      (node (ref "C5") (pin "2") (pinfunction "2_2") (pintype "passive"))
      (node (ref "C6") (pin "2") (pinfunction "2_2") (pintype "passive"))
      (node (ref "C7") (pin "2") (pinfunction "2_2") (pintype "passive"))
      (node (ref "C8") (pin "2") (pinfunction "2_2") (pintype "passive"))
      (node (ref "IC1") (pin "1") (pinfunction "VSS_1") (pintype "bidirectional"))
      (node (ref "IC2") (pin "2") (pinfunction "GND_2") (pintype "bidirectional"))
      (node (ref "IC2") (pin "EPAD") (pinfunction "GND_EPAD") (pintype "bidirectional"))
      (node (ref "IC3") (pin "13") (pinfunction "V-_13") (pintype "power_in"))
      (node (ref "IC3") (pin "PAD") (pinfunction "V-_PAD") (pintype "power_in"))
      (node (ref "IC5") (pin "12") (pinfunction "V-_12") (pintype "power_in"))
      (node (ref "IC5") (pin "16") (pinfunction "V-_16") (pintype "power_in"))
      (node (ref "IC5") (pin "18") (pinfunction "V-_18") (pintype "power_in"))
      (node (ref "IC5") (pin "21") (pinfunction "V-_21") (pintype "power_in"))
      (node (ref "IC5") (pin "27") (pinfunction "V-_27") (pintype "power_in"))
      (node (ref "IC5") (pin "3") (pinfunction "V-_3") (pintype "power_in"))
      (node (ref "IC5") (pin "30") (pinfunction "V-_30") (pintype "power_in"))
      (node (ref "IC5") (pin "31") (pinfunction "V-_31") (pintype "power_in"))
      (node (ref "IC5") (pin "32") (pinfunction "V-_32") (pintype "power_in"))
      (node (ref "IC5") (pin "6") (pinfunction "V-_6") (pintype "power_in"))
      (node (ref "IC5") (pin "7") (pinfunction "V-_7") (pintype "power_in"))
      (node (ref "IC5") (pin "PAD") (pinfunction "V-_PAD") (pintype "power_in"))
      (node (ref "IC7") (pin "1") (pinfunction "AISEN_1") (pintype "bidirectional"))
      (node (ref "IC7") (pin "11") (pinfunction "V-_11") (pintype "power_in"))
      (node (ref "IC7") (pin "4") (pinfunction "BISEN_4") (pintype "bidirectional"))
      (node (ref "IC7") (pin "PPAD") (pinfunction "V-_PPAD") (pintype "power_in"))
      (node (ref "IC8") (pin "1") (pinfunction "AISEN_1") (pintype "bidirectional"))
      (node (ref "IC8") (pin "11") (pinfunction "V-_11") (pintype "power_in"))
      (node (ref "IC8") (pin "4") (pinfunction "BISEN_4") (pintype "bidirectional"))
      (node (ref "IC8") (pin "PPAD") (pinfunction "V-_PPAD") (pintype "power_in"))
      (node (ref "IC9") (pin "1") (pinfunction "CLKIN_1") (pintype "bidirectional"))
      (node (ref "IC9") (pin "18") (pinfunction "V-_18") (pintype "power_in"))
      (node (ref "J1") (pin "6") (pinfunction "VSS_6") (pintype "power_in"))
      (node (ref "JP1") (pin "2") (pinfunction "2_2") (pintype "passive"))
      (node (ref "JP2") (pin "3") (pinfunction "3_3") (pintype "passive"))
      (node (ref "JP2") (pin "5") (pinfunction "5_5") (pintype "passive"))
      (node (ref "JP3") (pin "2") (pinfunction "2_2") (pintype "passive"))
      (node (ref "JP3") (pin "4") (pinfunction "4_4") (pintype "passive"))
      (node (ref "JP3") (pin "6") (pinfunction "6_6") (pintype "passive"))
      (node (ref "JP6") (pin "GND") (pinfunction "GND_GND") (pintype "bidirectional"))
      (node (ref "OSC2") (pin "2") (pinfunction "GND_2") (pintype "bidirectional"))
      (node (ref "OSC2") (pin "4") (pinfunction "GND_4") (pintype "bidirectional"))
      (node (ref "P2") (pin "1") (pinfunction "P_1") (pintype "passive"))
      (node (ref "R2") (pin "1") (pinfunction "1_1") (pintype "passive"))
      (node (ref "R26") (pin "2") (pinfunction "2_2") (pintype "passive"))
      (node (ref "R27") (pin "2") (pinfunction "2_2") (pintype "passive"))
      (node (ref "R28") (pin "2") (pinfunction "2_2") (pintype "passive"))
      (node (ref "R6") (pin "2") (pinfunction "2_2") (pintype "passive"))
      (node (ref "U$4") (pin "6") (pinfunction "VSS_6") (pintype "bidirectional"))
      (node (ref "U$4") (pin "PAD") (pinfunction "EP_PAD") (pintype "bidirectional"))
      (node (ref "U1") (pin "25") (pinfunction "VSSD2_25") (pintype "bidirectional"))
      (node (ref "U1") (pin "43") (pinfunction "VSSA_43") (pintype "bidirectional"))
      (node (ref "U1") (pin "45") (pinfunction "VSSD3_45") (pintype "bidirectional"))
      (node (ref "U1") (pin "58") (pinfunction "VSSD4_58") (pintype "bidirectional"))
      (node (ref "U1") (pin "9") (pinfunction "VSSD_9") (pintype "bidirectional"))
      (node (ref "U1") (pin "CENTER_PAD") (pinfunction "VSSD_PAD_CENTER_PAD") (pintype "bidirectional"))
      (node (ref "U2") (pin "2") (pinfunction "GND_2") (pintype "bidirectional"))
    )
    (net (code "16") (name "GN_LED") (class "Default")
      (node (ref "LED2") (pin "A") (pinfunction "A_A") (pintype "passive"))
      (node (ref "U1") (pin "3") (pinfunction "GREEN_LED_3") (pintype "bidirectional"))
    )
    (net (code "18") (name "IMU_IRQ") (class "Default")
      (node (ref "IC9") (pin "12") (pinfunction "INT_12") (pintype "bidirectional"))
    )
    (net (code "19") (name "IND") (class "Default")
      (node (ref "D1") (pin "A") (pinfunction "A_A") (pintype "passive"))
      (node (ref "L1") (pin "P$2") (pinfunction "2_P$2") (pintype "passive"))
      (node (ref "U1") (pin "6") (pinfunction "IND_6") (pintype "bidirectional"))
    )
    (net (code "20") (name "LOWBATT_IRQ") (class "Default")
      (node (ref "IC1") (pin "2") (pinfunction "VOUT_2") (pintype "bidirectional"))
    )
    (net (code "21") (name "MOTOR_A_BEMF") (class "Default")
      (node (ref "C41") (pin "1") (pinfunction "1_1") (pintype "passive"))
      (node (ref "R3") (pin "1") (pinfunction "1_1") (pintype "passive"))
      (node (ref "U1") (pin "28") (pinfunction "BEMFA_28") (pintype "bidirectional"))
    )
    (net (code "22") (name "MOTOR_A_IN1") (class "Default")
      (node (ref "IC7") (pin "14") (pinfunction "AIN1_14") (pintype "bidirectional"))
      (node (ref "U1") (pin "18") (pinfunction "PWMA_1_18") (pintype "bidirectional"))
    )
    (net (code "23") (name "MOTOR_A_IN2") (class "Default")
      (node (ref "IC7") (pin "13") (pinfunction "AIN2_13") (pintype "bidirectional"))
      (node (ref "U1") (pin "19") (pinfunction "PWMA_2_19") (pintype "bidirectional"))
    )
    (net (code "24") (name "MOTOR_A_OUT1") (class "Default")
      (node (ref "C24") (pin "1") (pinfunction "1_1") (pintype "passive"))
      (node (ref "IC7") (pin "16") (pinfunction "AOUT1_16") (pintype "bidirectional"))
      (node (ref "P3") (pin "1") (pinfunction "P_1") (pintype "passive"))
      (node (ref "R29") (pin "2") (pinfunction "2_2") (pintype "passive"))
    )
    (net (code "25") (name "MOTOR_A_OUT2") (class "Default")
      (node (ref "C24") (pin "2") (pinfunction "2_2") (pintype "passive"))
      (node (ref "IC7") (pin "2") (pinfunction "AOUT2_2") (pintype "bidirectional"))
      (node (ref "P4") (pin "1") (pinfunction "P_1") (pintype "passive"))
      (node (ref "R25") (pin "2") (pinfunction "2_2") (pintype "passive"))
    )
    (net (code "26") (name "MOTOR_B_BEMF") (class "Default")
      (node (ref "C42") (pin "1") (pinfunction "1_1") (pintype "passive"))
      (node (ref "R9") (pin "1") (pinfunction "1_1") (pintype "passive"))
      (node (ref "U1") (pin "27") (pinfunction "BEMFB_27") (pintype "bidirectional"))
    )
    (net (code "27") (name "MOTOR_B_IN1") (class "Default")
      (node (ref "IC7") (pin "7") (pinfunction "BIN1_7") (pintype "bidirectional"))
      (node (ref "U1") (pin "21") (pinfunction "PWMB_1_21") (pintype "bidirectional"))
    )
    (net (code "28") (name "MOTOR_B_IN2") (class "Default")
      (node (ref "IC7") (pin "8") (pinfunction "BIN2_8") (pintype "bidirectional"))
      (node (ref "U1") (pin "20") (pinfunction "PWMB_2_20") (pintype "bidirectional"))
    )
    (net (code "29") (name "MOTOR_B_OUT1") (class "Default")
      (node (ref "C25") (pin "1") (pinfunction "1_1") (pintype "passive"))
      (node (ref "IC7") (pin "5") (pinfunction "BOUT1_5") (pintype "bidirectional"))
      (node (ref "P5") (pin "1") (pinfunction "P_1") (pintype "passive"))
      (node (ref "R23") (pin "2") (pinfunction "2_2") (pintype "passive"))
    )
    (net (code "30") (name "MOTOR_B_OUT2") (class "Default")
      (node (ref "C25") (pin "2") (pinfunction "2_2") (pintype "passive"))
      (node (ref "IC7") (pin "3") (pinfunction "BOUT2_3") (pintype "bidirectional"))
      (node (ref "P6") (pin "1") (pinfunction "P_1") (pintype "passive"))
      (node (ref "R24") (pin "2") (pinfunction "2_2") (pintype "passive"))
    )
    (net (code "31") (name "MOTOR_C_BEMF") (class "Default")
      (node (ref "C43") (pin "1") (pinfunction "1_1") (pintype "passive"))
      (node (ref "R10") (pin "1") (pinfunction "1_1") (pintype "passive"))
      (node (ref "U1") (pin "30") (pinfunction "BEMFC_30") (pintype "bidirectional"))
    )
    (net (code "32") (name "MOTOR_C_IN1") (class "Default")
      (node (ref "IC8") (pin "14") (pinfunction "AIN1_14") (pintype "bidirectional"))
      (node (ref "U1") (pin "31") (pinfunction "PWMC_1_31") (pintype "bidirectional"))
    )
    (net (code "33") (name "MOTOR_C_IN2") (class "Default")
      (node (ref "IC8") (pin "13") (pinfunction "AIN2_13") (pintype "bidirectional"))
      (node (ref "U1") (pin "32") (pinfunction "PWMC_2_32") (pintype "bidirectional"))
    )
    (net (code "34") (name "MOTOR_C_OUT1") (class "Default")
      (node (ref "C27") (pin "1") (pinfunction "1_1") (pintype "passive"))
      (node (ref "IC8") (pin "16") (pinfunction "AOUT1_16") (pintype "bidirectional"))
      (node (ref "P7") (pin "1") (pinfunction "P_1") (pintype "passive"))
      (node (ref "R22") (pin "2") (pinfunction "2_2") (pintype "passive"))
    )
    (net (code "35") (name "MOTOR_C_OUT2") (class "Default")
      (node (ref "C27") (pin "2") (pinfunction "2_2") (pintype "passive"))
      (node (ref "IC8") (pin "2") (pinfunction "AOUT2_2") (pintype "bidirectional"))
      (node (ref "P8") (pin "1") (pinfunction "P_1") (pintype "passive"))
      (node (ref "R21") (pin "2") (pinfunction "2_2") (pintype "passive"))
    )
    (net (code "36") (name "MOTOR_D_BEMF") (class "Default")
      (node (ref "C44") (pin "1") (pinfunction "1_1") (pintype "passive"))
      (node (ref "R11") (pin "1") (pinfunction "1_1") (pintype "passive"))
      (node (ref "U1") (pin "29") (pinfunction "BEMFD_29") (pintype "bidirectional"))
    )
    (net (code "37") (name "MOTOR_D_IN1") (class "Default")
      (node (ref "IC8") (pin "7") (pinfunction "BIN1_7") (pintype "bidirectional"))
      (node (ref "U1") (pin "34") (pinfunction "PWMD_1_34") (pintype "bidirectional"))
    )
    (net (code "38") (name "MOTOR_D_IN2") (class "Default")
      (node (ref "IC8") (pin "8") (pinfunction "BIN2_8") (pintype "bidirectional"))
      (node (ref "U1") (pin "33") (pinfunction "PWMD_2_33") (pintype "bidirectional"))
    )
    (net (code "39") (name "MOTOR_D_OUT1") (class "Default")
      (node (ref "C28") (pin "1") (pinfunction "1_1") (pintype "passive"))
      (node (ref "IC8") (pin "5") (pinfunction "BOUT1_5") (pintype "bidirectional"))
      (node (ref "P9") (pin "1") (pinfunction "P_1") (pintype "passive"))
      (node (ref "R20") (pin "2") (pinfunction "2_2") (pintype "passive"))
    )
    (net (code "40") (name "MOTOR_D_OUT2") (class "Default")
      (node (ref "C28") (pin "2") (pinfunction "2_2") (pintype "passive"))
      (node (ref "IC8") (pin "3") (pinfunction "BOUT2_3") (pintype "bidirectional"))
      (node (ref "P10") (pin "1") (pinfunction "P_1") (pintype "passive"))
      (node (ref "R19") (pin "2") (pinfunction "2_2") (pintype "passive"))
    )
    (net (code "41") (name "Net-(ANT1-SIGNAL)") (class "Default")
      (node (ref "ANT1") (pin "A") (pinfunction "SIGNAL_A") (pintype "bidirectional"))
      (node (ref "B1") (pin "1") (pinfunction "UNBAL_1") (pintype "bidirectional"))
    )
    (net (code "42") (name "Net-(B1-BAL3)") (class "Default")
      (node (ref "B1") (pin "3") (pinfunction "BAL3_3") (pintype "bidirectional"))
      (node (ref "C17") (pin "1") (pinfunction "1_1") (pintype "passive"))
    )
    (net (code "43") (name "Net-(B1-BAL4)") (class "Default")
      (node (ref "B1") (pin "4") (pinfunction "BAL4_4") (pintype "bidirectional"))
      (node (ref "C16") (pin "2") (pinfunction "2_2") (pintype "passive"))
    )
    (net (code "44") (name "Net-(C22-Pad2)") (class "Default")
      (node (ref "C22") (pin "2") (pinfunction "2_2") (pintype "passive"))
      (node (ref "IC5") (pin "13") (pinfunction "V+_13") (pintype "power_in"))
      (node (ref "IC5") (pin "14") (pinfunction "V+_14") (pintype "power_in"))
    )
    (net (code "45") (name "Net-(IC3A-+IN)") (class "Default")
      (node (ref "IC3") (pin "3") (pinfunction "+IN_3") (pintype "input"))
      (node (ref "R14") (pin "2") (pinfunction "2_2") (pintype "passive"))
      (node (ref "R22") (pin "1") (pinfunction "1_1") (pintype "passive"))
    )
    (net (code "46") (name "Net-(IC3A--IN)") (class "Default")
      (node (ref "IC3") (pin "2") (pinfunction "-IN_2") (pintype "input"))
      (node (ref "R17") (pin "1") (pinfunction "1_1") (pintype "passive"))
      (node (ref "R21") (pin "1") (pinfunction "1_1") (pintype "passive"))
    )
    (net (code "47") (name "Net-(IC3A-OUT)") (class "Default")
      (node (ref "IC3") (pin "1") (pinfunction "OUT_1") (pintype "output"))
      (node (ref "R10") (pin "2") (pinfunction "2_2") (pintype "passive"))
      (node (ref "R14") (pin "1") (pinfunction "1_1") (pintype "passive"))
    )
    (net (code "48") (name "Net-(IC3B-+IN)") (class "Default")
      (node (ref "IC3") (pin "5") (pinfunction "+IN_5") (pintype "input"))
      (node (ref "R15") (pin "2") (pinfunction "2_2") (pintype "passive"))
      (node (ref "R20") (pin "1") (pinfunction "1_1") (pintype "passive"))
    )
    (net (code "49") (name "Net-(IC3B--IN)") (class "Default")
      (node (ref "IC3") (pin "6") (pinfunction "-IN_6") (pintype "input"))
      (node (ref "R18") (pin "1") (pinfunction "1_1") (pintype "passive"))
      (node (ref "R19") (pin "1") (pinfunction "1_1") (pintype "passive"))
    )
    (net (code "50") (name "Net-(IC3B-OUT)") (class "Default")
      (node (ref "IC3") (pin "7") (pinfunction "OUT_7") (pintype "output"))
      (node (ref "R11") (pin "2") (pinfunction "2_2") (pintype "passive"))
      (node (ref "R15") (pin "1") (pinfunction "1_1") (pintype "passive"))
    )
    (net (code "51") (name "Net-(IC3C-+IN)") (class "Default")
      (node (ref "IC3") (pin "12") (pinfunction "+IN_12") (pintype "input"))
      (node (ref "R12") (pin "2") (pinfunction "2_2") (pintype "passive"))
      (node (ref "R29") (pin "1") (pinfunction "1_1") (pintype "passive"))
    )
    (net (code "52") (name "Net-(IC3C--IN)") (class "Default")
      (node (ref "IC3") (pin "11") (pinfunction "-IN_11") (pintype "input"))
      (node (ref "R25") (pin "1") (pinfunction "1_1") (pintype "passive"))
      (node (ref "R8") (pin "1") (pinfunction "1_1") (pintype "passive"))
    )
    (net (code "53") (name "Net-(IC3C-OUT)") (class "Default")
      (node (ref "IC3") (pin "10") (pinfunction "OUT_10") (pintype "output"))
      (node (ref "R12") (pin "1") (pinfunction "1_1") (pintype "passive"))
      (node (ref "R3") (pin "2") (pinfunction "2_2") (pintype "passive"))
    )
    (net (code "54") (name "Net-(IC3D-+IN)") (class "Default")
      (node (ref "IC3") (pin "14") (pinfunction "+IN_14") (pintype "input"))
      (node (ref "R13") (pin "2") (pinfunction "2_2") (pintype "passive"))
      (node (ref "R24") (pin "1") (pinfunction "1_1") (pintype "passive"))
    )
    (net (code "55") (name "Net-(IC3D--IN)") (class "Default")
      (node (ref "IC3") (pin "15") (pinfunction "-IN_15") (pintype "input"))
      (node (ref "R16") (pin "1") (pinfunction "1_1") (pintype "passive"))
      (node (ref "R23") (pin "1") (pinfunction "1_1") (pintype "passive"))
    )
    (net (code "56") (name "Net-(IC3D-OUT)") (class "Default")
      (node (ref "IC3") (pin "16") (pinfunction "OUT_16") (pintype "output"))
      (node (ref "R13") (pin "1") (pinfunction "1_1") (pintype "passive"))
      (node (ref "R9") (pin "2") (pinfunction "2_2") (pintype "passive"))
    )
    (net (code "57") (name "Net-(IC5A-V+)") (class "Default")
      (node (ref "C20") (pin "2") (pinfunction "2_2") (pintype "passive"))
      (node (ref "IC5") (pin "29") (pinfunction "V+_29") (pintype "power_in"))
    )
    (net (code "58") (name "Net-(IC5G-RFN)") (class "Default")
      (node (ref "C17") (pin "2") (pinfunction "2_2") (pintype "passive"))
      (node (ref "IC5") (pin "5") (pinfunction "RFN_5") (pintype "bidirectional"))
    )
    (net (code "59") (name "Net-(IC5G-RFP)") (class "Default")
      (node (ref "C16") (pin "1") (pinfunction "1_1") (pintype "passive"))
      (node (ref "IC5") (pin "4") (pinfunction "RFP_4") (pintype "bidirectional"))
    )
    (net (code "60") (name "Net-(IC5G-XTAL1)") (class "Default")
      (node (ref "C18") (pin "1") (pinfunction "1_1") (pintype "passive"))
      (node (ref "IC5") (pin "26") (pinfunction "XTAL1_26") (pintype "bidirectional"))
      (node (ref "OSC2") (pin "1") (pinfunction "IN/OUT_1") (pintype "bidirectional"))
    )
    (net (code "61") (name "Net-(IC5G-XTAL2)") (class "Default")
      (node (ref "C19") (pin "1") (pinfunction "1_1") (pintype "passive"))
      (node (ref "IC5") (pin "25") (pinfunction "XTAL2_25") (pintype "bidirectional"))
      (node (ref "OSC2") (pin "3") (pinfunction "OUT/IN_3") (pintype "bidirectional"))
    )
    (net (code "62") (name "Net-(IC7A-V+)") (class "Default")
      (node (ref "C31") (pin "2") (pinfunction "2_2") (pintype "passive"))
      (node (ref "IC7") (pin "9") (pinfunction "V+_9") (pintype "power_in"))
    )
    (net (code "63") (name "Net-(IC7B-V-)") (class "Default")
      (node (ref "C32") (pin "1") (pinfunction "1_1") (pintype "passive"))
      (node (ref "IC7") (pin "12") (pinfunction "V-_12") (pintype "power_in"))
    )
    (net (code "64") (name "Net-(IC8A-V+)") (class "Default")
      (node (ref "C34") (pin "2") (pinfunction "2_2") (pintype "passive"))
      (node (ref "IC8") (pin "9") (pinfunction "V+_9") (pintype "power_in"))
    )
    (net (code "65") (name "Net-(IC8B-V-)") (class "Default")
      (node (ref "C35") (pin "1") (pinfunction "1_1") (pintype "passive"))
      (node (ref "IC8") (pin "12") (pinfunction "V-_12") (pintype "power_in"))
    )
    (net (code "66") (name "Net-(IC9A-V-)") (class "Default")
      (node (ref "C38") (pin "2") (pinfunction "2_2") (pintype "passive"))
      (node (ref "IC9") (pin "20") (pinfunction "V-_20") (pintype "power_in"))
    )
    (net (code "67") (name "Net-(IC9B-V-)") (class "Default")
      (node (ref "C39") (pin "2") (pinfunction "2_2") (pintype "passive"))
      (node (ref "IC9") (pin "10") (pinfunction "V-_10") (pintype "power_in"))
    )
    (net (code "68") (name "Net-(LED1-PadC)") (class "Default")
      (node (ref "LED1") (pin "C") (pinfunction "C_C") (pintype "passive"))
      (node (ref "R26") (pin "1") (pinfunction "1_1") (pintype "passive"))
    )
    (net (code "69") (name "Net-(LED2-PadC)") (class "Default")
      (node (ref "LED2") (pin "C") (pinfunction "C_C") (pintype "passive"))
      (node (ref "R27") (pin "1") (pinfunction "1_1") (pintype "passive"))
    )
    (net (code "70") (name "Net-(LED3-PadC)") (class "Default")
      (node (ref "LED3") (pin "C") (pinfunction "C_C") (pintype "passive"))
      (node (ref "R28") (pin "1") (pinfunction "1_1") (pintype "passive"))
    )
    (net (code "71") (name "Net-(LED4-PadC)") (class "Default")
      (node (ref "LED4") (pin "C") (pinfunction "C_C") (pintype "passive"))
      (node (ref "R7") (pin "1") (pinfunction "1_1") (pintype "passive"))
    )
    (net (code "72") (name "Net-(U$4-PROG)") (class "Default")
      (node (ref "R6") (pin "1") (pinfunction "1_1") (pintype "passive"))
      (node (ref "U$4") (pin "8") (pinfunction "PROG_8") (pintype "bidirectional"))
    )
    (net (code "73") (name "Net-(U$4-STAT)") (class "Default")
      (node (ref "R7") (pin "2") (pinfunction "2_2") (pintype "passive"))
      (node (ref "U$4") (pin "5") (pinfunction "STAT_5") (pintype "bidirectional"))
    )
    (net (code "74") (name "RADIO_IRQ") (class "Default")
      (node (ref "IC5") (pin "24") (pinfunction "IRQ_24") (pintype "bidirectional"))
      (node (ref "U1") (pin "46") (pinfunction "RADIO_IRQ_46") (pintype "bidirectional"))
    )
    (net (code "75") (name "RADIO_SLP_TR") (class "Default")
      (node (ref "IC5") (pin "11") (pinfunction "SLP_TR_11") (pintype "bidirectional"))
      (node (ref "U1") (pin "51") (pinfunction "RADIO_SLP_TR_51") (pintype "bidirectional"))
    )
    (net (code "76") (name "RADIO_~{RST}") (class "Default")
      (node (ref "IC5") (pin "8") (pinfunction "~{RST}_8") (pintype "bidirectional"))
      (node (ref "U1") (pin "60") (pinfunction "RADIO_~{RST}_60") (pintype "bidirectional"))
    )
    (net (code "77") (name "RD_LED") (class "Default")
      (node (ref "LED3") (pin "A") (pinfunction "A_A") (pintype "passive"))
      (node (ref "U1") (pin "2") (pinfunction "RED_LED_2") (pintype "bidirectional"))
    )
    (net (code "78") (name "SCK1") (class "Default")
      (node (ref "IC5") (pin "19") (pinfunction "SCLK_19") (pintype "bidirectional"))
      (node (ref "U1") (pin "50") (pinfunction "SCK1_50") (pintype "bidirectional"))
    )
    (net (code "79") (name "SCK2") (class "Default")
      (node (ref "IC9") (pin "23") (pinfunction "SCL/SCLK_23") (pintype "bidirectional"))
      (node (ref "U1") (pin "41") (pinfunction "SCK2_41") (pintype "bidirectional"))
    )
    (net (code "80") (name "SCL1") (class "Default")
      (node (ref "JP3") (pin "3") (pinfunction "3_3") (pintype "passive"))
      (node (ref "R4") (pin "1") (pinfunction "1_1") (pintype "passive"))
      (node (ref "U1") (pin "53") (pinfunction "SCL1_53") (pintype "bidirectional"))
    )
    (net (code "81") (name "SDA1") (class "Default")
      (node (ref "JP3") (pin "5") (pinfunction "5_5") (pintype "passive"))
      (node (ref "R5") (pin "1") (pinfunction "1_1") (pintype "passive"))
      (node (ref "U1") (pin "54") (pinfunction "SDA1_54") (pintype "bidirectional"))
    )
    (net (code "82") (name "SDI1") (class "Default")
      (node (ref "IC5") (pin "20") (pinfunction "MISO_20") (pintype "bidirectional"))
      (node (ref "U1") (pin "49") (pinfunction "MISO1_49") (pintype "bidirectional"))
    )
    (net (code "83") (name "SDI2") (class "Default")
      (node (ref "IC9") (pin "9") (pinfunction "AD0/SDO_9") (pintype "bidirectional"))
      (node (ref "U1") (pin "38") (pinfunction "MISO2_38") (pintype "bidirectional"))
    )
    (net (code "84") (name "SDO1") (class "Default")
      (node (ref "IC5") (pin "22") (pinfunction "MOSI_22") (pintype "bidirectional"))
      (node (ref "U1") (pin "48") (pinfunction "MOSI1_48") (pintype "bidirectional"))
    )
    (net (code "85") (name "SDO2") (class "Default")
      (node (ref "IC9") (pin "24") (pinfunction "SDA/SDI_24") (pintype "bidirectional"))
      (node (ref "U1") (pin "40") (pinfunction "MOSI2_40") (pintype "bidirectional"))
    )
    (net (code "86") (name "SWD_SCLK") (class "Default")
      (node (ref "JP1") (pin "5") (pinfunction "5_5") (pintype "passive"))
      (node (ref "U1") (pin "12") (pinfunction "SWDCK_12") (pintype "input"))
    )
    (net (code "87") (name "SWD_SDAT") (class "Default")
      (node (ref "JP1") (pin "4") (pinfunction "4_4") (pintype "passive"))
      (node (ref "U1") (pin "11") (pinfunction "SWDIO_11") (pintype "bidirectional"))
    )
    (net (code "88") (name "U1RX") (class "Default")
      (node (ref "JP2") (pin "6") (pinfunction "6_6") (pintype "passive"))
      (node (ref "U1") (pin "1") (pinfunction "U1RX_1") (pintype "bidirectional"))
    )
    (net (code "89") (name "U1TX") (class "Default")
      (node (ref "JP2") (pin "4") (pinfunction "4_4") (pintype "passive"))
      (node (ref "U1") (pin "68") (pinfunction "U1TX_68") (pintype "bidirectional"))
    )
    (net (code "90") (name "USB_D+") (class "Default")
      (node (ref "JP6") (pin "D+") (pinfunction "D+_D+") (pintype "bidirectional"))
      (node (ref "U1") (pin "55") (pinfunction "USB_D+_55") (pintype "bidirectional"))
    )
    (net (code "91") (name "USB_D-") (class "Default")
      (node (ref "JP6") (pin "D-") (pinfunction "D-_D-") (pintype "bidirectional"))
      (node (ref "U1") (pin "56") (pinfunction "USB_D-_56") (pintype "bidirectional"))
    )
    (net (code "92") (name "VBOOST") (class "Default")
      (node (ref "U1") (pin "7") (pinfunction "VBOOST_7") (pintype "bidirectional"))
    )
    (net (code "93") (name "VCCA") (class "Default")
      (node (ref "C14") (pin "1") (pinfunction "1_1") (pintype "passive"))
      (node (ref "U1") (pin "42") (pinfunction "VCCA_42") (pintype "bidirectional"))
    )
    (net (code "94") (name "VCCD") (class "Default")
      (node (ref "C40") (pin "1") (pinfunction "1_1") (pintype "passive"))
      (node (ref "U1") (pin "26") (pinfunction "VCCD_26") (pintype "bidirectional"))
      (node (ref "U1") (pin "57") (pinfunction "VCCD2_57") (pintype "bidirectional"))
    )
    (net (code "95") (name "VSSBOOST") (class "Default")
      (node (ref "C9") (pin "2") (pinfunction "2_2") (pintype "passive"))
      (node (ref "U1") (pin "5") (pinfunction "VSSBOOST_5") (pintype "bidirectional"))
    )
    (net (code "96") (name "V_BATT") (class "Default")
      (node (ref "C3") (pin "1") (pinfunction "1_1") (pintype "passive"))
      (node (ref "C30") (pin "1") (pinfunction "1_1") (pintype "passive"))
      (node (ref "C31") (pin "1") (pinfunction "1_1") (pintype "passive"))
      (node (ref "C33") (pin "1") (pinfunction "1_1") (pintype "passive"))
      (node (ref "C34") (pin "1") (pinfunction "1_1") (pintype "passive"))
      (node (ref "C4") (pin "2") (pinfunction "2_2") (pintype "passive"))
      (node (ref "IC1") (pin "3") (pinfunction "VIN_3") (pintype "bidirectional"))
      (node (ref "IC2") (pin "1") (pinfunction "VIN_1") (pintype "bidirectional"))
      (node (ref "IC2") (pin "3") (pinfunction "EN_3.0V_3") (pintype "bidirectional"))
      (node (ref "IC2") (pin "4") (pinfunction "EN_3.3V_4") (pintype "bidirectional"))
      (node (ref "IC7") (pin "10") (pinfunction "V+_10") (pintype "power_in"))
      (node (ref "IC7") (pin "15") (pinfunction "~{SLEEP}_15") (pintype "bidirectional"))
      (node (ref "IC8") (pin "10") (pinfunction "V+_10") (pintype "power_in"))
      (node (ref "IC8") (pin "15") (pinfunction "~{SLEEP}_15") (pintype "bidirectional"))
      (node (ref "JP2") (pin "1") (pinfunction "1_1") (pintype "passive"))
      (node (ref "JP2") (pin "2") (pinfunction "2_2") (pintype "passive"))
      (node (ref "P1") (pin "1") (pinfunction "P_1") (pintype "passive"))
      (node (ref "R1") (pin "2") (pinfunction "2_2") (pintype "passive"))
      (node (ref "U$4") (pin "3") (pinfunction "VBAT_3") (pintype "bidirectional"))
      (node (ref "U$4") (pin "4") (pinfunction "VBAT_4") (pintype "bidirectional"))
    )
    (net (code "97") (name "V_BOOSTED_4.2V") (class "Default")
      (node (ref "C9") (pin "1") (pinfunction "1_1") (pintype "passive"))
      (node (ref "L1") (pin "P$1") (pinfunction "1_P$1") (pintype "passive"))
      (node (ref "U1") (pin "8") (pinfunction "VBAT_8") (pintype "bidirectional"))
    )
    (net (code "98") (name "V_REF") (class "Default")
      (node (ref "C26") (pin "1") (pinfunction "1_1") (pintype "passive"))
      (node (ref "R16") (pin "2") (pinfunction "2_2") (pintype "passive"))
      (node (ref "R17") (pin "2") (pinfunction "2_2") (pintype "passive"))
      (node (ref "R18") (pin "2") (pinfunction "2_2") (pintype "passive"))
      (node (ref "R8") (pin "2") (pinfunction "2_2") (pintype "passive"))
      (node (ref "U1") (pin "23") (pinfunction "VREF_OUT_23") (pintype "bidirectional"))
    )
    (net (code "99") (name "YW_LED") (class "Default")
      (node (ref "LED1") (pin "A") (pinfunction "A_A") (pintype "passive"))
      (node (ref "U1") (pin "4") (pinfunction "YELLOW_LED_4") (pintype "bidirectional"))
    )
    (net (code "100") (name "unconnected-(B1-NC-Pad6)") (class "Default")
      (node (ref "B1") (pin "6") (pinfunction "NC_6") (pintype "bidirectional"))
    )
    (net (code "101") (name "unconnected-(C13-Pad2)") (class "Default")
      (node (ref "C13") (pin "2") (pinfunction "2_2") (pintype "passive"))
    )
    (net (code "102") (name "unconnected-(IC5G-CLKM-Pad17)") (class "Default")
      (node (ref "IC5") (pin "17") (pinfunction "CLKM_17") (pintype "bidirectional"))
    )
    (net (code "103") (name "unconnected-(IC5G-DIG1-Pad9)") (class "Default")
      (node (ref "IC5") (pin "9") (pinfunction "DIG1_9") (pintype "bidirectional"))
    )
    (net (code "104") (name "unconnected-(IC5G-DIG2-Pad10)") (class "Default")
      (node (ref "IC5") (pin "10") (pinfunction "DIG2_10") (pintype "bidirectional"))
    )
    (net (code "105") (name "unconnected-(IC5G-DIG3-Pad1)") (class "Default")
      (node (ref "IC5") (pin "1") (pinfunction "DIG3_1") (pintype "bidirectional"))
    )
    (net (code "106") (name "unconnected-(IC5G-DIG4-Pad2)") (class "Default")
      (node (ref "IC5") (pin "2") (pinfunction "DIG4_2") (pintype "bidirectional"))
    )
    (net (code "107") (name "unconnected-(IC7D-~{FAULT}-Pad6)") (class "Default")
      (node (ref "IC7") (pin "6") (pinfunction "~{FAULT}_6") (pintype "bidirectional"))
    )
    (net (code "108") (name "unconnected-(IC8D-~{FAULT}-Pad6)") (class "Default")
      (node (ref "IC8") (pin "6") (pinfunction "~{FAULT}_6") (pintype "bidirectional"))
    )
    (net (code "109") (name "unconnected-(IC9D-AUX_CL-Pad7)") (class "Default")
      (node (ref "IC9") (pin "7") (pinfunction "AUX_CL_7") (pintype "bidirectional"))
    )
    (net (code "110") (name "unconnected-(IC9D-AUX_DA-Pad6)") (class "Default")
      (node (ref "IC9") (pin "6") (pinfunction "AUX_DA_6") (pintype "bidirectional"))
    )
    (net (code "111") (name "unconnected-(IC9D-CLKOUT-Pad22)") (class "Default")
      (node (ref "IC9") (pin "22") (pinfunction "CLKOUT_22") (pintype "bidirectional"))
    )
    (net (code "112") (name "unconnected-(J1-DAT1-Pad8)") (class "Default")
      (node (ref "J1") (pin "8") (pinfunction "DAT1_8") (pintype "bidirectional"))
    )
    (net (code "113") (name "unconnected-(J1-DAT2-Pad1)") (class "Default")
      (node (ref "J1") (pin "1") (pinfunction "DAT2_1") (pintype "bidirectional"))
    )
    (net (code "114") (name "unconnected-(JP1-Pad6)") (class "Default")
      (node (ref "JP1") (pin "6") (pinfunction "6_6") (pintype "passive"))
    )
    (net (code "115") (name "unconnected-(U1D-LOWBATT_IRQ-Pad62)") (class "Default")
      (node (ref "U1") (pin "62") (pinfunction "LOWBATT_IRQ_62") (pintype "bidirectional"))
    )
    (net (code "116") (name "~{SS1}") (class "Default")
      (node (ref "IC5") (pin "23") (pinfunction "~{SEL}_23") (pintype "bidirectional"))
      (node (ref "U1") (pin "47") (pinfunction "/SS1_47") (pintype "bidirectional"))
    )
    (net (code "117") (name "~{SS2}") (class "Default")
      (node (ref "IC9") (pin "8") (pinfunction "~{CS}_8") (pintype "bidirectional"))
      (node (ref "U1") (pin "39") (pinfunction "/SS2_39") (pintype "bidirectional"))
    )
    (net (code "118") (name "~{XRES}") (class "Default")
      (node (ref "JP1") (pin "3") (pinfunction "3_3") (pintype "passive"))
      (node (ref "U1") (pin "10") (pinfunction "~{XRES}_10") (pintype "bidirectional"))
    )
  )
)
